# ngff-cardem.net
KiCad netlist of a schematic drawn in EAGLE
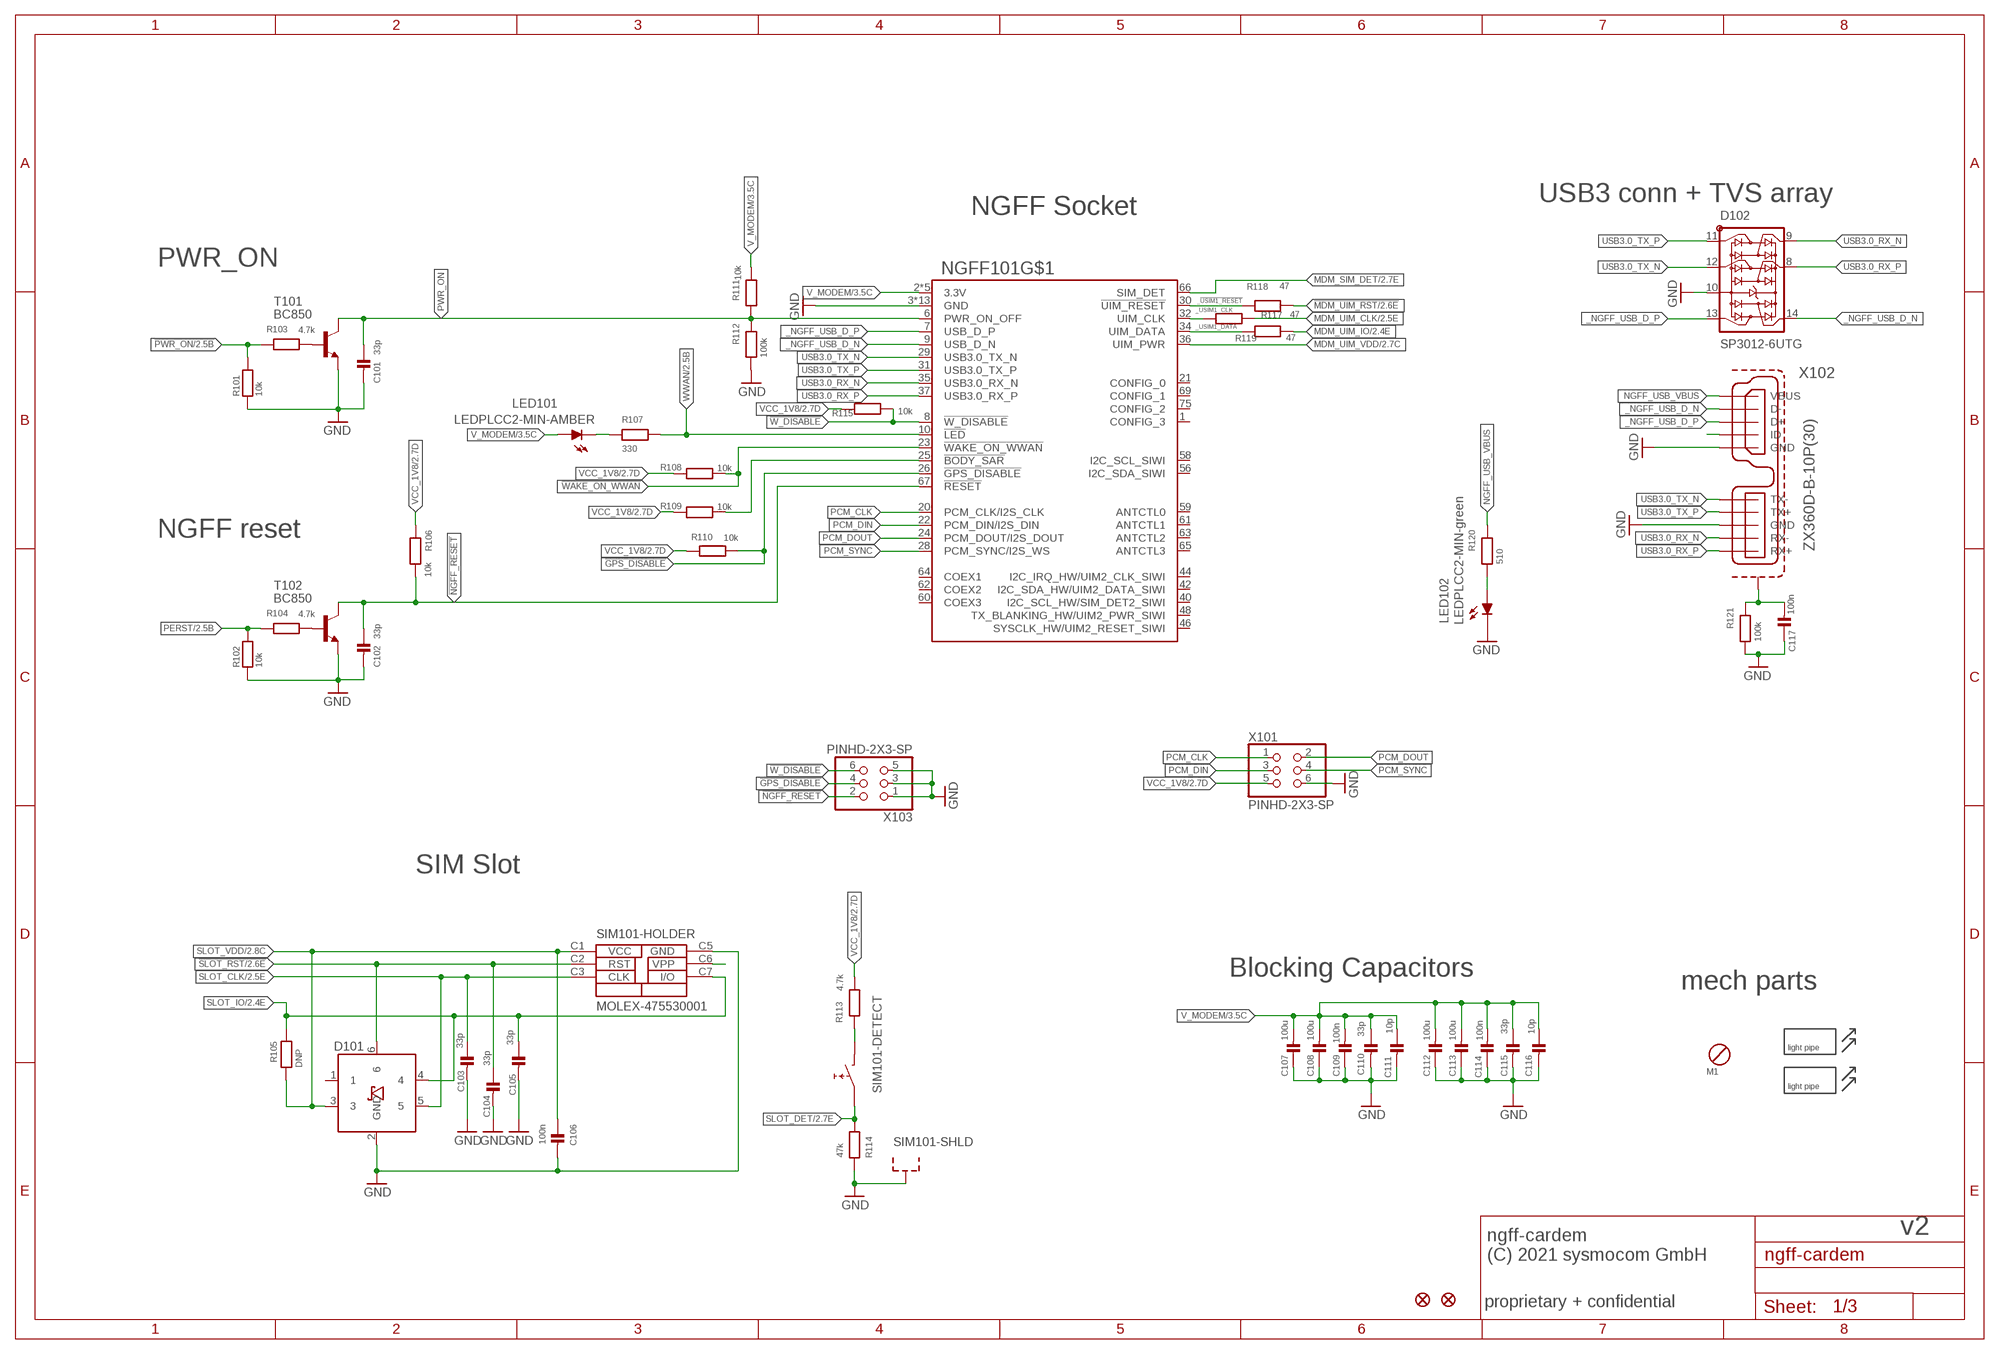
[diagram p0: schematic, sheet 1]
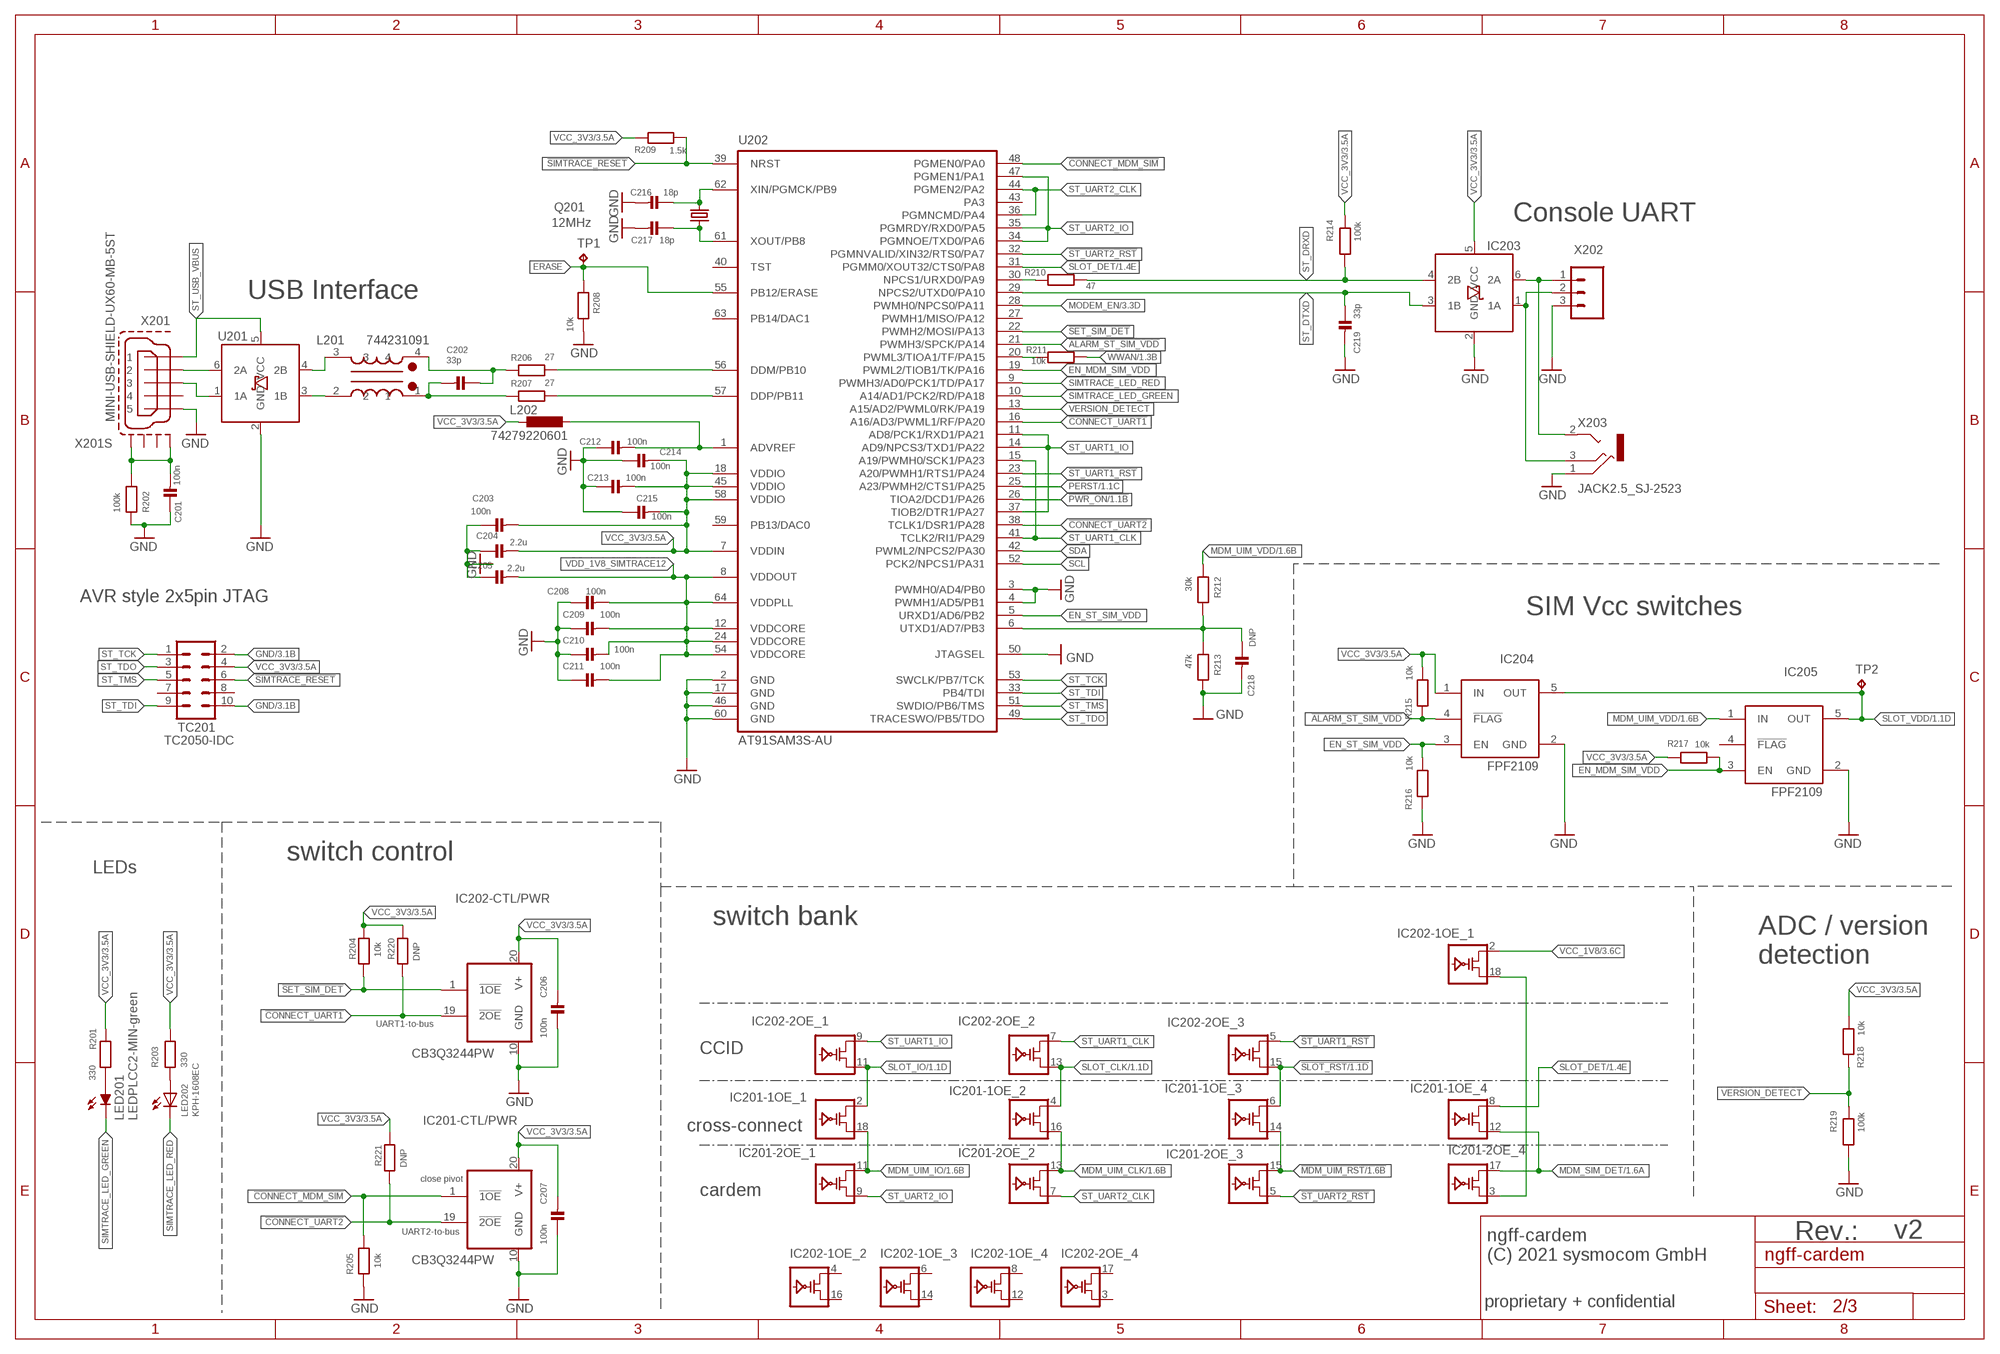
[diagram p1: schematic, sheet 2]
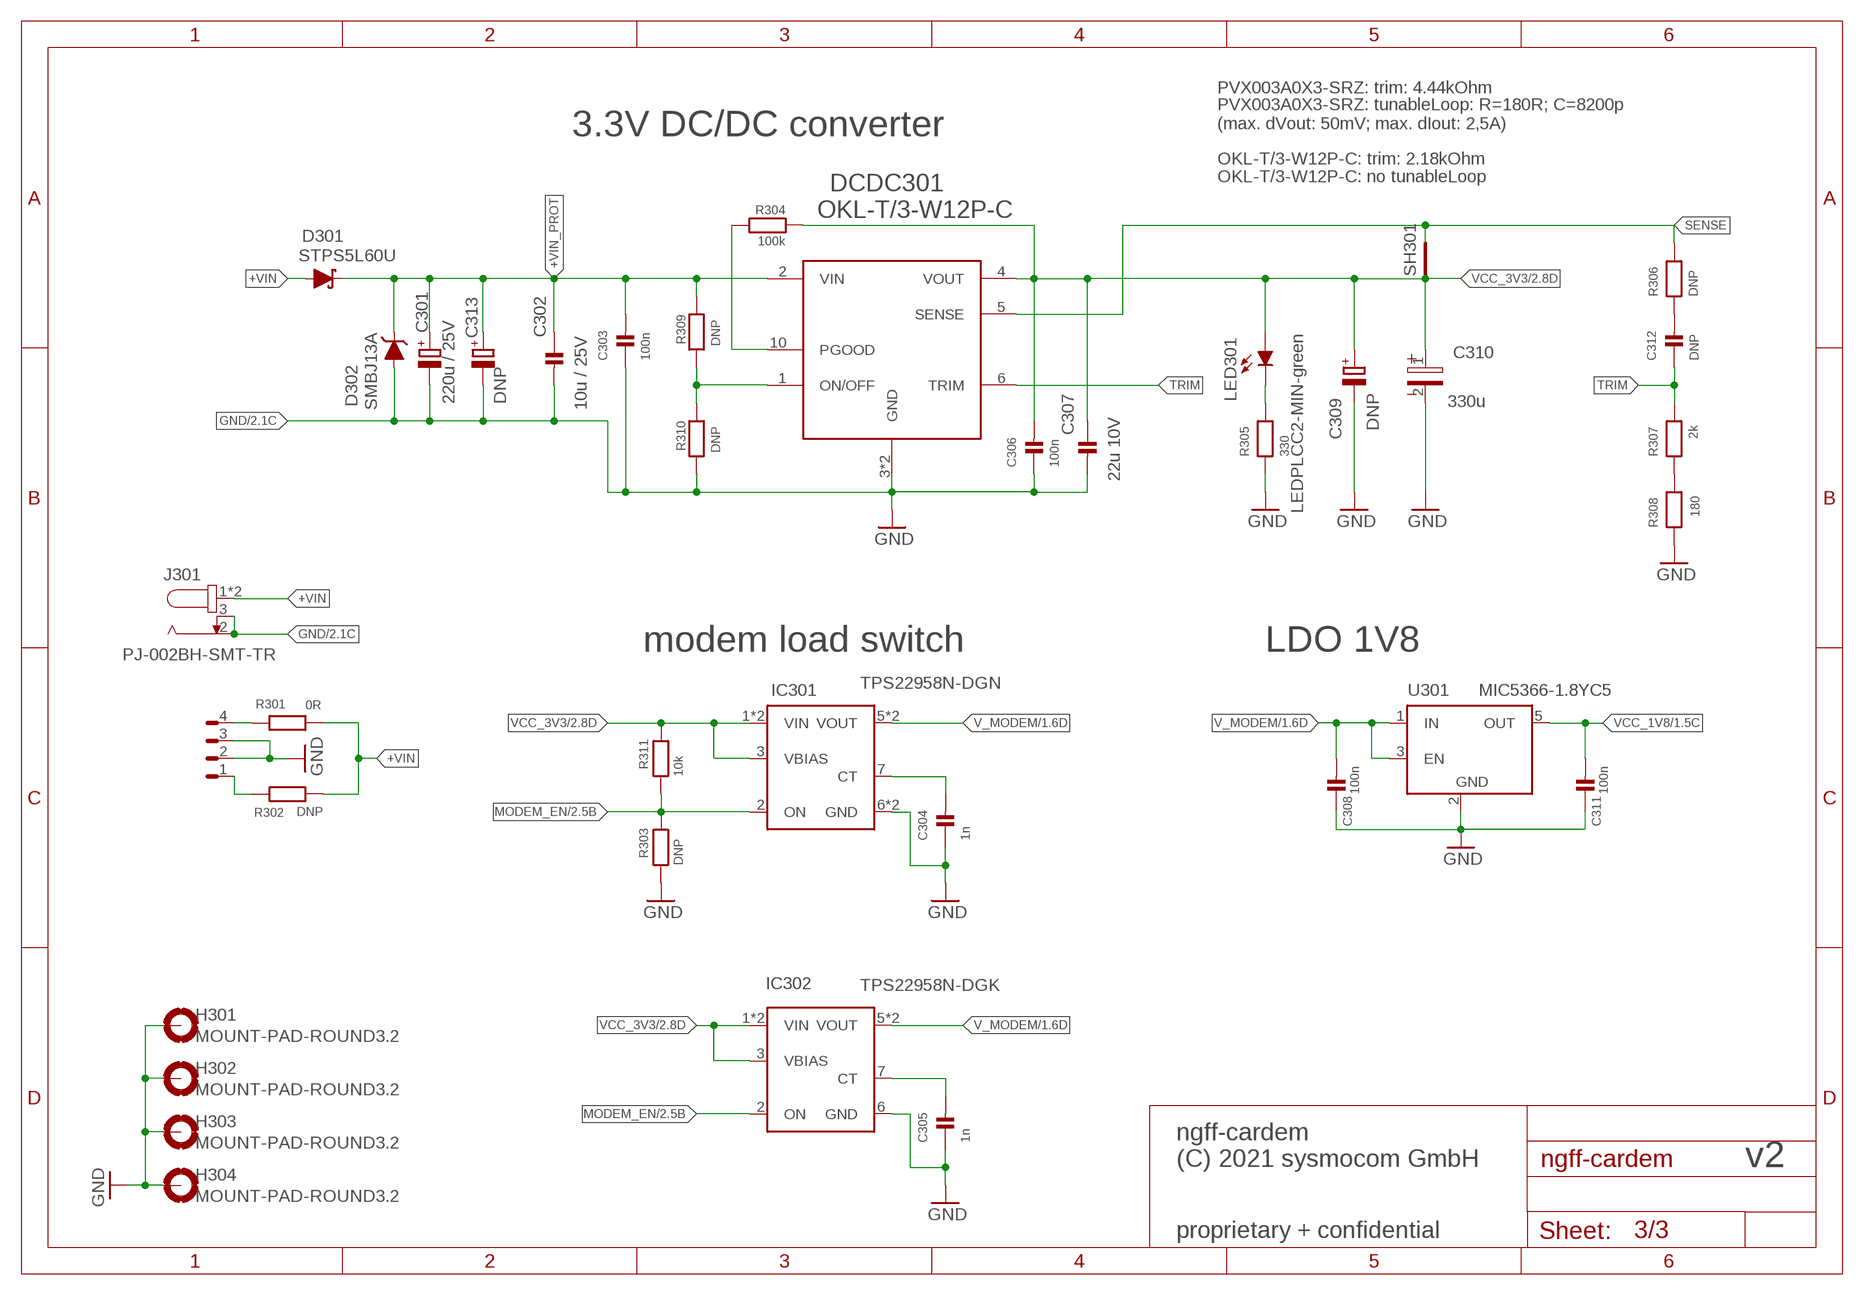
[diagram p2: schematic, sheet 3]

(export (version "E")
  (design (tool "Eeschema 10.0.6"))
  (components
    (comp (ref "C101")
      (value "33p")
      (footprint "eagle-import:_0402")
      (description "CAP CER 33PF 50V NP0 0402")
      (fields
        (field (name "MANUFACTURER") "Samsung Electro-Mechanics America, Inc.")
        (field (name "MANUFACTURERPARTNUMBER") "CL05C330JB5NNNC")
      )
      (libsource (lib "eagle-import") (part "CAP_CERAMIC_0402"))
    )
    (comp (ref "C102")
      (value "33p")
      (footprint "eagle-import:_0402")
      (description "CAP CER 33PF 50V NP0 0402")
      (fields
        (field (name "MANUFACTURER") "Samsung Electro-Mechanics America, Inc.")
        (field (name "MANUFACTURERPARTNUMBER") "CL05C330JB5NNNC")
      )
      (libsource (lib "eagle-import") (part "CAP_CERAMIC_0402"))
    )
    (comp (ref "C103")
      (value "33p")
      (footprint "eagle-import:_0402")
      (description "CAP CER 33PF 50V NP0 0402")
      (fields
        (field (name "MANUFACTURER") "Samsung Electro-Mechanics America, Inc.")
        (field (name "MANUFACTURERPARTNUMBER") "CL05C330JB5NNNC")
      )
      (libsource (lib "eagle-import") (part "CAP_CERAMIC_0402"))
    )
    (comp (ref "C104")
      (value "33p")
      (footprint "eagle-import:_0402")
      (description "CAP CER 33PF 50V NP0 0402")
      (fields
        (field (name "MANUFACTURER") "Samsung Electro-Mechanics America, Inc.")
        (field (name "MANUFACTURERPARTNUMBER") "CL05C330JB5NNNC")
      )
      (libsource (lib "eagle-import") (part "CAP_CERAMIC_0402"))
    )
    (comp (ref "C105")
      (value "33p")
      (footprint "eagle-import:_0402")
      (description "CAP CER 33PF 50V NP0 0402")
      (fields
        (field (name "MANUFACTURER") "Samsung Electro-Mechanics America, Inc.")
        (field (name "MANUFACTURERPARTNUMBER") "CL05C330JB5NNNC")
      )
      (libsource (lib "eagle-import") (part "CAP_CERAMIC_0402"))
    )
    (comp (ref "C106")
      (value "100n")
      (footprint "eagle-import:_0603")
      (description "CAP CER 0.1UF 16V X7R 0603")
      (fields
        (field (name "MANUFACTURER") "Yageo")
        (field (name "MANUFACTURERPARTNUMBER") "CC0603KRX7R7BB104")
      )
      (libsource (lib "eagle-import") (part "CAP_CERAMIC_0603"))
    )
    (comp (ref "C107")
      (value "100u")
      (footprint "eagle-import:1206")
      (description "CAP CER 100UF 6.3V X5R 1206")
      (fields
        (field (name "MANUFACTURER") "TDK Corporation")
        (field (name "MANUFACTURERPARTNUMBER") "C3216X5R0J107M160AB")
      )
      (libsource (lib "eagle-import") (part "CAP_CERAMIC1206"))
    )
    (comp (ref "C108")
      (value "100u")
      (footprint "eagle-import:1206")
      (description "CAP CER 100UF 6.3V X5R 1206")
      (fields
        (field (name "MANUFACTURER") "TDK Corporation")
        (field (name "MANUFACTURERPARTNUMBER") "C3216X5R0J107M160AB")
      )
      (libsource (lib "eagle-import") (part "CAP_CERAMIC1206"))
    )
    (comp (ref "C109")
      (value "100n")
      (footprint "eagle-import:_0603")
      (description "CAP CER 0.1UF 16V X7R 0603")
      (fields
        (field (name "MANUFACTURER") "Yageo")
        (field (name "MANUFACTURERPARTNUMBER") "CC0603KRX7R7BB104")
      )
      (libsource (lib "eagle-import") (part "CAP_CERAMIC_0603"))
    )
    (comp (ref "C110")
      (value "33p")
      (footprint "eagle-import:_0402")
      (description "CAP CER 33PF 50V NP0 0402")
      (fields
        (field (name "MANUFACTURER") "Samsung Electro-Mechanics America, Inc.")
        (field (name "MANUFACTURERPARTNUMBER") "CL05C330JB5NNNC")
      )
      (libsource (lib "eagle-import") (part "CAP_CERAMIC_0402"))
    )
    (comp (ref "C111")
      (value "10p")
      (footprint "eagle-import:_0603")
      (description "CAP CER 10PF 50V C0G/NP0 0603")
      (fields
        (field (name "MANUFACTURER") "KEMET")
        (field (name "MANUFACTURERPARTNUMBER") "C0603C100F5GAC7867")
      )
      (libsource (lib "eagle-import") (part "CAP_CERAMIC_0603"))
    )
    (comp (ref "C112")
      (value "100u")
      (footprint "eagle-import:1206")
      (description "CAP CER 100UF 6.3V X5R 1206")
      (fields
        (field (name "MANUFACTURER") "TDK Corporation")
        (field (name "MANUFACTURERPARTNUMBER") "C3216X5R0J107M160AB")
      )
      (libsource (lib "eagle-import") (part "CAP_CERAMIC1206"))
    )
    (comp (ref "C113")
      (value "100u")
      (footprint "eagle-import:1206")
      (description "CAP CER 100UF 6.3V X5R 1206")
      (fields
        (field (name "MANUFACTURER") "TDK Corporation")
        (field (name "MANUFACTURERPARTNUMBER") "C3216X5R0J107M160AB")
      )
      (libsource (lib "eagle-import") (part "CAP_CERAMIC1206"))
    )
    (comp (ref "C114")
      (value "100n")
      (footprint "eagle-import:_0603")
      (description "CAP CER 0.1UF 16V X7R 0603")
      (fields
        (field (name "MANUFACTURER") "Yageo")
        (field (name "MANUFACTURERPARTNUMBER") "CC0603KRX7R7BB104")
      )
      (libsource (lib "eagle-import") (part "CAP_CERAMIC_0603"))
    )
    (comp (ref "C115")
      (value "33p")
      (footprint "eagle-import:_0402")
      (description "CAP CER 33PF 50V NP0 0402")
      (fields
        (field (name "MANUFACTURER") "Samsung Electro-Mechanics America, Inc.")
        (field (name "MANUFACTURERPARTNUMBER") "CL05C330JB5NNNC")
      )
      (libsource (lib "eagle-import") (part "CAP_CERAMIC_0402"))
    )
    (comp (ref "C116")
      (value "10p")
      (footprint "eagle-import:_0603")
      (description "CAP CER 10PF 50V C0G/NP0 0603")
      (fields
        (field (name "MANUFACTURER") "KEMET")
        (field (name "MANUFACTURERPARTNUMBER") "C0603C100F5GAC7867")
      )
      (libsource (lib "eagle-import") (part "CAP_CERAMIC_0603"))
    )
    (comp (ref "C117")
      (value "100n")
      (footprint "eagle-import:_0603")
      (description "CAP CER 0.1UF 16V X7R 0603")
      (fields
        (field (name "MANUFACTURER") "Yageo")
        (field (name "MANUFACTURERPARTNUMBER") "CC0603KRX7R7BB104")
      )
      (libsource (lib "eagle-import") (part "CAP_CERAMIC_0603"))
    )
    (comp (ref "D101")
      (value "PESD5V0UBV")
      (footprint "eagle-import:SOT666")
      (description "TVS DIODE 5V SOT666")
      (fields
        (field (name "MANUFACTURER") "Nexperia USA Inc.")
        (field (name "MANUFACTURERPARTNUMBER") "PESD5V0U5BV,115")
      )
      (libsource (lib "eagle-import") (part "PESD5V0UBV"))
    )
    (comp (ref "D102")
      (value "SP3012-6UTG")
      (footprint "eagle-import:UDFN-14")
      (description "TVS DIODE 5V 7V 14UDFN")
      (fields
        (field (name "MANUFACTURER") "Littelfuse Inc.")
        (field (name "MANUFACTURERPARTNUMBER") "SP3012-06UTG")
      )
      (libsource (lib "eagle-import") (part "SP3012-6UTG"))
    )
    (comp (ref "JP102")
      (value "FIDUCIALUFIDUCIAL")
      (footprint "eagle-import:MICRO-FIDUCIAL")
      (description "NO DESCRIPTION")
      (fields
        (field (name "MANUFACTURER") "UNKNOWN MANUFACTURER")
        (field (name "MANUFACTURERPARTNUMBER") "UNKNOWN MANUFACTURER PART NUMBER")
      )
      (libsource (lib "eagle-import") (part "FIDUCIALUFIDUCIAL"))
    )
    (comp (ref "JP103")
      (value "FIDUCIALUFIDUCIAL")
      (footprint "eagle-import:MICRO-FIDUCIAL")
      (description "NO DESCRIPTION")
      (fields
        (field (name "MANUFACTURER") "UNKNOWN MANUFACTURER")
        (field (name "MANUFACTURERPARTNUMBER") "UNKNOWN MANUFACTURER PART NUMBER")
      )
      (libsource (lib "eagle-import") (part "FIDUCIALUFIDUCIAL"))
    )
    (comp (ref "LED101")
      (value "LEDPLCC2-MIN-AMBER")
      (footprint "eagle-import:PLCC2-MIN")
      (description "LED ORANGE CLEAR 2PLCC SMD")
      (fields
        (field (name "MANUFACTURER") "OSRAM Opto Semiconductors Inc.")
        (field (name "MANUFACTURERPARTNUMBER") "LO T676-S1T1-24-Z")
      )
      (libsource (lib "eagle-import") (part "LEDPLCC2-MIN"))
    )
    (comp (ref "LED102")
      (value "LEDPLCC2-MIN-green")
      (footprint "eagle-import:PLCC2-MIN")
      (description "LED GREEN CLEAR 2PLCC SMD")
      (fields
        (field (name "MANUFACTURER") "Broadcom Limited")
        (field (name "MANUFACTURERPARTNUMBER") "HSME-A100-M02J1")
      )
      (libsource (lib "eagle-import") (part "LEDPLCC2-MIN"))
    )
    (comp (ref "M2")
      (value "MENTOR_12701001")
      (footprint "eagle-import:1270.1001")
      (description "NO DESCRIPTION")
      (fields
        (field (name "MANUFACTURER") "UNKNOWN MANUFACTURER")
        (field (name "MANUFACTURERPARTNUMBER") "UNKNOWN MANUFACTURER PART NUMBER")
      )
      (libsource (lib "eagle-import") (part "MENTOR_12701001"))
    )
    (comp (ref "M3")
      (value "MENTOR_12701001")
      (footprint "eagle-import:1270.1001")
      (description "NO DESCRIPTION")
      (fields
        (field (name "MANUFACTURER") "UNKNOWN MANUFACTURER")
        (field (name "MANUFACTURERPARTNUMBER") "UNKNOWN MANUFACTURER PART NUMBER")
      )
      (libsource (lib "eagle-import") (part "MENTOR_12701001"))
    )
    (comp (ref "NGFF101")
      (value "NGFF_B-NSOL")
      (footprint "eagle-import:NGFF_3042_3052_NSOL")
      (description "CONN FEMALE 67POS 0.020 GOLD")
      (fields
        (field (name "MANUFACTURER") "TE Connectivity AMP Connectors")
        (field (name "MANUFACTURERPARTNUMBER") "2199230-3")
      )
      (libsource (lib "eagle-import") (part "NGFF_B-NSOL"))
    )
    (comp (ref "R101")
      (value "10k")
      (footprint "eagle-import:_0603")
      (description "RES SMD 10K OHM 1%% 1/10W 0603")
      (fields
        (field (name "MANUFACTURER") "TE Connectivity Passive Product")
        (field (name "MANUFACTURERPARTNUMBER") "CRG0603F10K/10")
      )
      (libsource (lib "eagle-import") (part "RESISTOR_0603"))
    )
    (comp (ref "R102")
      (value "10k")
      (footprint "eagle-import:_0603")
      (description "RES SMD 10K OHM 1%% 1/10W 0603")
      (fields
        (field (name "MANUFACTURER") "TE Connectivity Passive Product")
        (field (name "MANUFACTURERPARTNUMBER") "CRG0603F10K/10")
      )
      (libsource (lib "eagle-import") (part "RESISTOR_0603"))
    )
    (comp (ref "R103")
      (value "4.7k")
      (footprint "eagle-import:_0603")
      (description "RES SMD 4.7K OHM 5% 1/10W 0603")
      (fields (field (name "MANUFACTURER") "Yageo") (field (name "MANUFACTURERPARTNUMBER") "RC0603JR-074K7L"))
      (libsource (lib "eagle-import") (part "RESISTOR_0603"))
    )
    (comp (ref "R104")
      (value "4.7k")
      (footprint "eagle-import:_0603")
      (description "RES SMD 4.7K OHM 5% 1/10W 0603")
      (fields (field (name "MANUFACTURER") "Yageo") (field (name "MANUFACTURERPARTNUMBER") "RC0603JR-074K7L"))
      (libsource (lib "eagle-import") (part "RESISTOR_0603"))
    )
    (comp (ref "R105")
      (value "DNP")
      (footprint "eagle-import:_0603")
      (description "RES SMD 10K OHM 1%% 1/10W 0603")
      (fields
        (field (name "MANUFACTURER") "TE Connectivity Passive Product")
        (field (name "MANUFACTURERPARTNUMBER") "CRG0603F10K/10")
      )
      (libsource (lib "eagle-import") (part "RESISTOR_0603"))
    )
    (comp (ref "R106")
      (value "10k")
      (footprint "eagle-import:_0603")
      (description "RES SMD 10K OHM 1%% 1/10W 0603")
      (fields
        (field (name "MANUFACTURER") "TE Connectivity Passive Product")
        (field (name "MANUFACTURERPARTNUMBER") "CRG0603F10K/10")
      )
      (libsource (lib "eagle-import") (part "RESISTOR_0603"))
    )
    (comp (ref "R107")
      (value "330")
      (footprint "eagle-import:_0603")
      (description "RES SMD 330 OHM 1%% 1/10W 0603")
      (fields
        (field (name "MANUFACTURER") "Yageo")
        (field (name "MANUFACTURERPARTNUMBER") "RC0603FR-07330RL")
      )
      (libsource (lib "eagle-import") (part "RESISTOR_0603"))
    )
    (comp (ref "R108")
      (value "10k")
      (footprint "eagle-import:_0603")
      (description "RES SMD 10K OHM 1%% 1/10W 0603")
      (fields
        (field (name "MANUFACTURER") "TE Connectivity Passive Product")
        (field (name "MANUFACTURERPARTNUMBER") "CRG0603F10K/10")
      )
      (libsource (lib "eagle-import") (part "RESISTOR_0603"))
    )
    (comp (ref "R109")
      (value "10k")
      (footprint "eagle-import:_0603")
      (description "RES SMD 10K OHM 1%% 1/10W 0603")
      (fields
        (field (name "MANUFACTURER") "TE Connectivity Passive Product")
        (field (name "MANUFACTURERPARTNUMBER") "CRG0603F10K/10")
      )
      (libsource (lib "eagle-import") (part "RESISTOR_0603"))
    )
    (comp (ref "R110")
      (value "10k")
      (footprint "eagle-import:_0603")
      (description "RES SMD 10K OHM 1%% 1/10W 0603")
      (fields
        (field (name "MANUFACTURER") "TE Connectivity Passive Product")
        (field (name "MANUFACTURERPARTNUMBER") "CRG0603F10K/10")
      )
      (libsource (lib "eagle-import") (part "RESISTOR_0603"))
    )
    (comp (ref "R111")
      (value "10k")
      (footprint "eagle-import:_0603")
      (description "RES SMD 10K OHM 1%% 1/10W 0603")
      (fields
        (field (name "MANUFACTURER") "TE Connectivity Passive Product")
        (field (name "MANUFACTURERPARTNUMBER") "CRG0603F10K/10")
      )
      (libsource (lib "eagle-import") (part "RESISTOR_0603"))
    )
    (comp (ref "R112")
      (value "100k")
      (footprint "eagle-import:_0603")
      (description "RES 100K OHM 1%% 1/10W 0603")
      (fields
        (field (name "MANUFACTURER") "Stackpole Electronics Inc")
        (field (name "MANUFACTURERPARTNUMBER") "RMCF0603FT100K")
      )
      (libsource (lib "eagle-import") (part "RESISTOR_0603"))
    )
    (comp (ref "R113")
      (value "4.7k")
      (footprint "eagle-import:_0603")
      (description "RES SMD 4.7K OHM 5% 1/10W 0603")
      (fields (field (name "MANUFACTURER") "Yageo") (field (name "MANUFACTURERPARTNUMBER") "RC0603JR-074K7L"))
      (libsource (lib "eagle-import") (part "RESISTOR_0603"))
    )
    (comp (ref "R114")
      (value "47k")
      (footprint "eagle-import:_0603")
      (description "RES 47K OHM 1%% 1/10W 0603")
      (fields
        (field (name "MANUFACTURER") "Stackpole Electronics Inc")
        (field (name "MANUFACTURERPARTNUMBER") "RMCF0603FT47K0")
      )
      (libsource (lib "eagle-import") (part "RESISTOR_0603"))
    )
    (comp (ref "R115")
      (value "10k")
      (footprint "eagle-import:_0603")
      (description "RES SMD 10K OHM 1%% 1/10W 0603")
      (fields
        (field (name "MANUFACTURER") "TE Connectivity Passive Product")
        (field (name "MANUFACTURERPARTNUMBER") "CRG0603F10K/10")
      )
      (libsource (lib "eagle-import") (part "RESISTOR_0603"))
    )
    (comp (ref "R117")
      (value "47")
      (footprint "eagle-import:_0402")
      (description "RES SMD 47R 0402 1%")
      (fields
        (field (name "MANUFACTURER") "TE Connectivity Passive Product")
        (field (name "MANUFACTURERPARTNUMBER") "CRGCQ0402F47R")
      )
      (libsource (lib "eagle-import") (part "RESISTOR_0402"))
    )
    (comp (ref "R118")
      (value "47")
      (footprint "eagle-import:_0402")
      (description "RES SMD 47R 0402 1%")
      (fields
        (field (name "MANUFACTURER") "TE Connectivity Passive Product")
        (field (name "MANUFACTURERPARTNUMBER") "CRGCQ0402F47R")
      )
      (libsource (lib "eagle-import") (part "RESISTOR_0402"))
    )
    (comp (ref "R119")
      (value "47")
      (footprint "eagle-import:_0402")
      (description "RES SMD 47R 0402 1%")
      (fields
        (field (name "MANUFACTURER") "TE Connectivity Passive Product")
        (field (name "MANUFACTURERPARTNUMBER") "CRGCQ0402F47R")
      )
      (libsource (lib "eagle-import") (part "RESISTOR_0402"))
    )
    (comp (ref "R120")
      (value "510")
      (footprint "eagle-import:_0603")
      (description "RES 510 OHM 1%% 1/10W 0603")
      (fields
        (field (name "MANUFACTURER") "Stackpole Electronics Inc")
        (field (name "MANUFACTURERPARTNUMBER") "RMCF0603FT510R")
      )
      (libsource (lib "eagle-import") (part "RESISTOR_0603"))
    )
    (comp (ref "R121")
      (value "100k")
      (footprint "eagle-import:_0603")
      (description "RES 100K OHM 1%% 1/10W 0603")
      (fields
        (field (name "MANUFACTURER") "Stackpole Electronics Inc")
        (field (name "MANUFACTURERPARTNUMBER") "RMCF0603FT100K")
      )
      (libsource (lib "eagle-import") (part "RESISTOR_0603"))
    )
    (comp (ref "SIM101")
      (value "MOLEX-475530001")
      (footprint "eagle-import:MOLEX-475530001")
      (description "CONN SIM CARD PUSH-PUSH R/A SMD")
      (fields
        (field (name "CLASS") "SIM HOLDER")
        (field (name "LINK") "https://www.digikey.de/product-detail/de/molex/0475530001/WM3293TR-ND/2404889")
        (field (name "MANUFACTURER") "Molex")
        (field (name "MANUFACTURERPARTNUMBER") "0475530001")
        (field (name "POPULATED") "TRUE")
        (field (name "ROHSCERTIFICATE") "RoHS3-konform")
        (field (name "SOURCE") "DIGIKEY")
        (field (name "SOURCEPARTNUMBER") "WM3293TR-ND")
      )
      (libsource (lib "eagle-import") (part "MOLEX-475530001"))
    )
    (comp (ref "T101")
      (value "BC850")
      (footprint "eagle-import:SOT23-BEC")
      (description "TRANS NPN 45V 100MA TO236AB")
      (fields
        (field (name "MANUFACTURER") "Nexperia USA Inc.")
        (field (name "MANUFACTURERPARTNUMBER") "BC850C,235")
      )
      (libsource (lib "eagle-import") (part "-NPN-SOT23-BECBC847C"))
    )
    (comp (ref "T102")
      (value "BC850")
      (footprint "eagle-import:SOT23-BEC")
      (description "TRANS NPN 45V 100MA TO236AB")
      (fields
        (field (name "MANUFACTURER") "Nexperia USA Inc.")
        (field (name "MANUFACTURERPARTNUMBER") "BC850C,235")
      )
      (libsource (lib "eagle-import") (part "-NPN-SOT23-BECBC847C"))
    )
    (comp (ref "X101")
      (value "PINHD-2X3-SP")
      (footprint "eagle-import:2X03")
      (description "PIN HEADER, THR, DUAL ROW, .100\"")
      (fields
        (field (name "MANUFACTURER") "METZ CONNECT USA Inc.")
        (field (name "MANUFACTURERPARTNUMBER") "PR20203VBDN")
      )
      (libsource (lib "eagle-import") (part "PINHD-2X3"))
    )
    (comp (ref "X102")
      (value "ZX360D-B-10P(30)")
      (footprint "eagle-import:ZX360D-B")
      (description "CONN RCPT USB3.0 MICRO B SMD R/A")
      (fields (field (name "MANUFACTURER") "Hirose Electric Co Ltd"))
      (libsource (lib "eagle-import") (part "USB3.0-MICROB"))
    )
    (comp (ref "X103")
      (value "PINHD-2X3-SP")
      (footprint "eagle-import:2X03")
      (description "PIN HEADER, THR, DUAL ROW, .100\"")
      (fields
        (field (name "MANUFACTURER") "METZ CONNECT USA Inc.")
        (field (name "MANUFACTURERPARTNUMBER") "PR20203VBDN")
      )
      (libsource (lib "eagle-import") (part "PINHD-2X3"))
    )
    (comp (ref "C301")
      (value "220u / 25V")
      (footprint "eagle-import:UD-8X10_NICHICON")
      (description "CAP ALUM 220UF 20%% 25V SMD")
      (fields
        (field (name "MANUFACTURER") "Nichicon")
        (field (name "MANUFACTURERPARTNUMBER") "UUD1E221MNL1GS")
      )
      (libsource (lib "eagle-import") (part "CPOL-EUUD-8X10"))
    )
    (comp (ref "C302")
      (value "10u / 25V")
      (footprint "eagle-import:C1812K")
      (description "CAP CER 10UF 25V X7R 1812")
      (fields
        (field (name "MANUFACTURER") "TDK Corporation")
        (field (name "MANUFACTURERPARTNUMBER") "C4532X7R1E106M250KA")
      )
      (libsource (lib "eagle-import") (part "CAP_CERAMIC-C1812"))
    )
    (comp (ref "C303")
      (value "100n")
      (footprint "eagle-import:_0603")
      (description "CAP CER 0.1UF 16V X7R 0603")
      (fields
        (field (name "MANUFACTURER") "Yageo")
        (field (name "MANUFACTURERPARTNUMBER") "CC0603KRX7R7BB104")
      )
      (libsource (lib "eagle-import") (part "CAP_CERAMIC_0603"))
    )
    (comp (ref "C304")
      (value "1n")
      (footprint "eagle-import:_0603")
      (description "CAP CER 1000PF 50V X7R 0603")
      (fields
        (field (name "MANUFACTURER") "Samsung Electro-Mechanics")
        (field (name "MANUFACTURERPARTNUMBER") "CL10B102KB8NNNC")
      )
      (libsource (lib "eagle-import") (part "CAP_CERAMIC_0603"))
    )
    (comp (ref "C305")
      (value "1n")
      (footprint "eagle-import:_0603")
      (description "CAP CER 1000PF 50V X7R 0603")
      (fields
        (field (name "MANUFACTURER") "Samsung Electro-Mechanics")
        (field (name "MANUFACTURERPARTNUMBER") "CL10B102KB8NNNC")
      )
      (libsource (lib "eagle-import") (part "CAP_CERAMIC_0603"))
    )
    (comp (ref "C306")
      (value "100n")
      (footprint "eagle-import:_0603")
      (description "CAP CER 0.1UF 16V X7R 0603")
      (fields
        (field (name "MANUFACTURER") "Yageo")
        (field (name "MANUFACTURERPARTNUMBER") "CC0603KRX7R7BB104")
      )
      (libsource (lib "eagle-import") (part "CAP_CERAMIC_0603"))
    )
    (comp (ref "C307")
      (value "22u 10V")
      (footprint "eagle-import:1206")
      (description "CAP CER 47UF 10V X5R 1206")
      (fields
        (field (name "MANUFACTURER") "Samsung Electro-Mechanics")
        (field (name "MANUFACTURERPARTNUMBER") "CL31A476MPHNNNE")
      )
      (libsource (lib "eagle-import") (part "CAP_CERAMIC1206"))
    )
    (comp (ref "C308")
      (value "100n")
      (footprint "eagle-import:_0603")
      (description "CAP CER 0.1UF 16V X7R 0603")
      (fields
        (field (name "MANUFACTURER") "Yageo")
        (field (name "MANUFACTURERPARTNUMBER") "CC0603KRX7R7BB104")
      )
      (libsource (lib "eagle-import") (part "CAP_CERAMIC_0603"))
    )
    (comp (ref "C309")
      (value "DNP")
      (footprint "eagle-import:SMC_B")
      (description "CAP TANT 100UF 6.3V 20% 1210")
      (fields
        (field (name "MANUFACTURER") "AVX Corporation")
        (field (name "MANUFACTURERPARTNUMBER") "F920J107MBA")
      )
      (libsource (lib "eagle-import") (part "CPOL-EUSMCB"))
    )
    (comp (ref "C310")
      (value "330u")
      (footprint "eagle-import:4.2X1.9X2.8(BXCXA)")
      (description "CAP ALUM POLY 330UF 20%% 6.3V SMD")
      (fields
        (field (name "MANUFACTURER") "United Chemi-Con")
        (field (name "MANUFACTURERPARTNUMBER") "APXF6R3ARA331MH70G")
      )
      (libsource (lib "eagle-import") (part "WCAP-PSLC_8X11.7(DXL)"))
    )
    (comp (ref "C311")
      (value "100n")
      (footprint "eagle-import:_0603")
      (description "CAP CER 0.1UF 16V X7R 0603")
      (fields
        (field (name "MANUFACTURER") "Yageo")
        (field (name "MANUFACTURERPARTNUMBER") "CC0603KRX7R7BB104")
      )
      (libsource (lib "eagle-import") (part "CAP_CERAMIC_0603"))
    )
    (comp (ref "C312")
      (value "DNP")
      (footprint "eagle-import:_0603")
      (description "NO DESCRIPTION")
      (fields
        (field (name "MANUFACTURER") "UNKNOWN MANUFACTURER")
        (field (name "MANUFACTURERPARTNUMBER") "UNKNOWN MANUFACTURER PART NUMBER")
      )
      (libsource (lib "eagle-import") (part "CAP_CERAMIC_0603"))
    )
    (comp (ref "C313")
      (value "DNP")
      (footprint "eagle-import:UD-8X10_NICHICON")
      (description "NO DESCRIPTION")
      (fields
        (field (name "MANUFACTURER") "UNKNOWN MANUFACTURER")
        (field (name "MANUFACTURERPARTNUMBER") "UNKNOWN MANUFACTURER PART NUMBER")
      )
      (libsource (lib "eagle-import") (part "CPOL-EUUD-8X10"))
    )
    (comp (ref "D301")
      (value "STPS5L60U")
      (footprint "eagle-import:SMBDIODE")
      (description "DIODE SCHOTTKY 50V 3A SMB")
      (fields
        (field (name "MANUFACTURER") "Diodes Incorporated")
        (field (name "MANUFACTURERPARTNUMBER") "B350B-13-F")
      )
      (libsource (lib "eagle-import") (part "DIODE-SCHOTTKY-SMB"))
    )
    (comp (ref "D302")
      (value "SMBJ13A")
      (footprint "eagle-import:SMBDIODE")
      (description "TVS DIODE 13.6VWM 22.5VC SMB")
      (fields
        (field (name "MANUFACTURER") "Littelfuse Inc.")
        (field (name "MANUFACTURERPARTNUMBER") "SZP6SMB16AT3G")
      )
      (libsource (lib "eagle-import") (part "DIODE-TVS-SMB"))
    )
    (comp (ref "DCDC301")
      (value "OKL-T/3-W12P-C")
      (footprint "eagle-import:DC-DC_CON-ALLPADS")
      (description "DC DC CONVERTER 0.591-5.5V 15W")
      (fields (field (name "MANUFACTURER") "Murata Power Solutions Inc."))
      (libsource (lib "eagle-import") (part "DCDC-GE-PVX-ALL"))
    )
    (comp (ref "H301")
      (value "MOUNT-PAD-ROUND3.2")
      (footprint "eagle-import:3,2-PAD")
      (description "NO DESCRIPTION")
      (fields
        (field (name "MANUFACTURER") "UNKNOWN MANUFACTURER")
        (field (name "MANUFACTURERPARTNUMBER") "UNKNOWN MANUFACTURER PART NUMBER")
      )
      (libsource (lib "eagle-import") (part "MOUNT-PAD-ROUND3.2"))
    )
    (comp (ref "H302")
      (value "MOUNT-PAD-ROUND3.2")
      (footprint "eagle-import:3,2-PAD")
      (description "NO DESCRIPTION")
      (fields
        (field (name "MANUFACTURER") "UNKNOWN MANUFACTURER")
        (field (name "MANUFACTURERPARTNUMBER") "UNKNOWN MANUFACTURER PART NUMBER")
      )
      (libsource (lib "eagle-import") (part "MOUNT-PAD-ROUND3.2"))
    )
    (comp (ref "H303")
      (value "MOUNT-PAD-ROUND3.2")
      (footprint "eagle-import:3,2-PAD")
      (description "NO DESCRIPTION")
      (fields
        (field (name "MANUFACTURER") "UNKNOWN MANUFACTURER")
        (field (name "MANUFACTURERPARTNUMBER") "UNKNOWN MANUFACTURER PART NUMBER")
      )
      (libsource (lib "eagle-import") (part "MOUNT-PAD-ROUND3.2"))
    )
    (comp (ref "H304")
      (value "MOUNT-PAD-ROUND3.2")
      (footprint "eagle-import:3,2-PAD")
      (description "NO DESCRIPTION")
      (fields
        (field (name "MANUFACTURER") "UNKNOWN MANUFACTURER")
        (field (name "MANUFACTURERPARTNUMBER") "UNKNOWN MANUFACTURER PART NUMBER")
      )
      (libsource (lib "eagle-import") (part "MOUNT-PAD-ROUND3.2"))
    )
    (comp (ref "IC301")
      (value "TPS22958N-DGN")
      (footprint "eagle-import:HVSSOP8")
      (description "IC PWR SWITCH N-CHAN 1:1 8MSOP")
      (fields
        (field (name "MANUFACTURER") "Texas Instruments")
        (field (name "MANUFACTURERPARTNUMBER") "TPS22958DGNR")
      )
      (libsource (lib "eagle-import") (part "TPS22958-DGNN"))
    )
    (comp (ref "IC302")
      (value "TPS22958N-DGK")
      (footprint "eagle-import:VSSOP8")
      (description "IC PWR SWITCH N-CHAN 1:1 8VSSOP")
      (fields
        (field (name "MANUFACTURER") "Texas Instruments")
        (field (name "MANUFACTURERPARTNUMBER") "TPS22958NDGKR")
      )
      (libsource (lib "eagle-import") (part "TPS22958-DGKN"))
    )
    (comp (ref "J301")
      (value "PJ-002BH-SMT-TR")
      (footprint "eagle-import:694108106102")
      (description "CONN PWR JACK 2.5X5.5MM SOLDER")
      (fields (field (name "MANUFACTURER") "CUI Devices"))
      (libsource (lib "eagle-import") (part "694108106102"))
    )
    (comp (ref "LED301")
      (value "LEDPLCC2-MIN-green")
      (footprint "eagle-import:PLCC2-MIN")
      (description "LED GREEN CLEAR 2PLCC SMD")
      (fields
        (field (name "MANUFACTURER") "Broadcom Limited")
        (field (name "MANUFACTURERPARTNUMBER") "HSME-A100-M02J1")
      )
      (libsource (lib "eagle-import") (part "LEDPLCC2-MIN"))
    )
    (comp (ref "R301")
      (value "0R")
      (footprint "eagle-import:1210")
      (description "RES 0 OHM JUMPER 1206")
      (fields
        (field (name "MANUFACTURER") "KOA Speer Electronics, Inc.")
        (field (name "MANUFACTURERPARTNUMBER") "TLRZ2BTTD")
      )
      (libsource (lib "eagle-import") (part "RESISTOR1210"))
    )
    (comp (ref "R302")
      (value "DNP")
      (footprint "eagle-import:1210")
      (description "RES 0 OHM JUMPER 1206")
      (fields
        (field (name "MANUFACTURER") "KOA Speer Electronics, Inc.")
        (field (name "MANUFACTURERPARTNUMBER") "TLRZ2BTTD")
      )
      (libsource (lib "eagle-import") (part "RESISTOR1210"))
    )
    (comp (ref "R303")
      (value "DNP")
      (footprint "eagle-import:_0603")
      (description "NO DESCRIPTION")
      (fields
        (field (name "MANUFACTURER") "UNKNOWN MANUFACTURER")
        (field (name "MANUFACTURERPARTNUMBER") "UNKNOWN MANUFACTURER PART NUMBER")
      )
      (libsource (lib "eagle-import") (part "RESISTOR_0603"))
    )
    (comp (ref "R304")
      (value "100k")
      (footprint "eagle-import:_0603")
      (description "RES 100K OHM 1%% 1/10W 0603")
      (fields
        (field (name "MANUFACTURER") "Stackpole Electronics Inc")
        (field (name "MANUFACTURERPARTNUMBER") "RMCF0603FT100K")
      )
      (libsource (lib "eagle-import") (part "RESISTOR_0603"))
    )
    (comp (ref "R305")
      (value "330")
      (footprint "eagle-import:_0603")
      (description "RES SMD 330 OHM 1%% 1/10W 0603")
      (fields
        (field (name "MANUFACTURER") "Yageo")
        (field (name "MANUFACTURERPARTNUMBER") "RC0603FR-07330RL")
      )
      (libsource (lib "eagle-import") (part "RESISTOR_0603"))
    )
    (comp (ref "R306")
      (value "DNP")
      (footprint "eagle-import:_0603")
      (description "NO DESCRIPTION")
      (fields
        (field (name "MANUFACTURER") "UNKNOWN MANUFACTURER")
        (field (name "MANUFACTURERPARTNUMBER") "UNKNOWN MANUFACTURER PART NUMBER")
      )
      (libsource (lib "eagle-import") (part "RESISTOR_0603"))
    )
    (comp (ref "R307")
      (value "2k")
      (footprint "eagle-import:_0603")
      (description "RES SMD 2K OHM 1% 1/10W 0603")
      (fields (field (name "MANUFACTURER") "YAGEO") (field (name "MANUFACTURERPARTNUMBER") "RC0603FR-072KL"))
      (libsource (lib "eagle-import") (part "RESISTOR_0603"))
    )
    (comp (ref "R308")
      (value "180")
      (footprint "eagle-import:_0603")
      (description "RES SMD 180R 1% 1/10W 0603")
      (fields
        (field (name "MANUFACTURER") "TE Connectivity Passive Product")
        (field (name "MANUFACTURERPARTNUMBER") "CRGCQ0603F180R")
      )
      (libsource (lib "eagle-import") (part "RESISTOR_0603"))
    )
    (comp (ref "R309")
      (value "DNP")
      (footprint "eagle-import:_0603")
      (description "NO DESCRIPTION")
      (fields
        (field (name "MANUFACTURER") "UNKNOWN MANUFACTURER")
        (field (name "MANUFACTURERPARTNUMBER") "UNKNOWN MANUFACTURER PART NUMBER")
      )
      (libsource (lib "eagle-import") (part "RESISTOR_0603"))
    )
    (comp (ref "R310")
      (value "DNP")
      (footprint "eagle-import:_0603")
      (description "NO DESCRIPTION")
      (fields
        (field (name "MANUFACTURER") "UNKNOWN MANUFACTURER")
        (field (name "MANUFACTURERPARTNUMBER") "UNKNOWN MANUFACTURER PART NUMBER")
      )
      (libsource (lib "eagle-import") (part "RESISTOR_0603"))
    )
    (comp (ref "R311")
      (value "10k")
      (footprint "eagle-import:_0603")
      (description "RES SMD 10K OHM 1%% 1/10W 0603")
      (fields
        (field (name "MANUFACTURER") "TE Connectivity Passive Product")
        (field (name "MANUFACTURERPARTNUMBER") "CRG0603F10K/10")
      )
      (libsource (lib "eagle-import") (part "RESISTOR_0603"))
    )
    (comp (ref "SH301")
      (value "SHORT-HT5")
      (footprint "eagle-import:SHORT_TOP-50")
      (description "NO DESCRIPTION")
      (fields
        (field (name "MANUFACTURER") "UNKNOWN MANUFACTURER")
        (field (name "MANUFACTURERPARTNUMBER") "UNKNOWN MANUFACTURER PART NUMBER")
      )
      (libsource (lib "eagle-import") (part "SHORT-HT5"))
    )
    (comp (ref "U301")
      (value "MIC5366-1.8YC5")
      (footprint "eagle-import:SC70-5")
      (description "IC REG LINEAR 1.8V 150MA SC70-5")
      (fields
        (field (name "MANUFACTURER") "Microchip Technology")
        (field (name "MANUFACTURERPARTNUMBER") "MIC5366-1.8YC5-TR")
      )
      (libsource (lib "eagle-import") (part "LDO_FIXED_EN-MIC5365-YC5"))
    )
    (comp (ref "X301")
      (value "171826-4-RA")
      (footprint "eagle-import:171826-4")
      (description "CONN HEADER R/A 4POS 2.5MM")
      (fields
        (field (name "MANUFACTURER") "TE Connectivity AMP Connectors")
        (field (name "MANUFACTURERPARTNUMBER") "171826-4")
        (field (name "CLASS") "CONNECTOR")
        (field (name "LINK") "https://www.digikey.de/product-detail/de/171826-4/A112643-ND")
        (field (name "POPULATED") "TRUE")
        (field (name "ROHSCERTIFICATE") "RoHS-konform")
        (field (name "SOURCE") "DIGIKEY")
        (field (name "SOURCEPARTNUMBER") "A112643-ND")
      )
      (libsource (lib "eagle-import") (part "171826-4-RA"))
    )
    (comp (ref "C201")
      (value "100n")
      (footprint "eagle-import:_0603")
      (description "CAP CER 0.1UF 16V X7R 0603")
      (fields
        (field (name "MANUFACTURER") "Yageo")
        (field (name "MANUFACTURERPARTNUMBER") "CC0603KRX7R7BB104")
      )
      (libsource (lib "eagle-import") (part "CAP_CERAMIC_0603"))
    )
    (comp (ref "C202")
      (value "33p")
      (footprint "eagle-import:_0402")
      (description "CAP CER 33PF 50V NP0 0402")
      (fields
        (field (name "MANUFACTURER") "Samsung Electro-Mechanics America, Inc.")
        (field (name "MANUFACTURERPARTNUMBER") "CL05C330JB5NNNC")
      )
      (libsource (lib "eagle-import") (part "CAP_CERAMIC_0402"))
    )
    (comp (ref "C203")
      (value "100n")
      (footprint "eagle-import:_0402")
      (description "CAP CER 0.1UF 16V X7R 0402")
      (fields
        (field (name "MANUFACTURER") "Samsung Electro-Mechanics")
        (field (name "MANUFACTURERPARTNUMBER") "CL05B104KO5NNWC")
      )
      (libsource (lib "eagle-import") (part "CAP_CERAMIC_0402"))
    )
    (comp (ref "C204")
      (value "2.2u")
      (footprint "eagle-import:_0603")
      (description "CAP CER 2.2UF 10V X5R 0603")
      (fields
        (field (name "MANUFACTURER") "AVX Corporation")
        (field (name "MANUFACTURERPARTNUMBER") "0603ZD225KAT2A")
      )
      (libsource (lib "eagle-import") (part "CAP_CERAMIC_0603"))
    )
    (comp (ref "C205")
      (value "2.2u")
      (footprint "eagle-import:_0603")
      (description "CAP CER 2.2UF 10V X5R 0603")
      (fields
        (field (name "MANUFACTURER") "AVX Corporation")
        (field (name "MANUFACTURERPARTNUMBER") "0603ZD225KAT2A")
      )
      (libsource (lib "eagle-import") (part "CAP_CERAMIC_0603"))
    )
    (comp (ref "C206")
      (value "100n")
      (footprint "eagle-import:_0402")
      (description "CAP CER 0.1UF 16V X7R 0402")
      (fields
        (field (name "MANUFACTURER") "Samsung Electro-Mechanics")
        (field (name "MANUFACTURERPARTNUMBER") "CL05B104KO5NNWC")
      )
      (libsource (lib "eagle-import") (part "CAP_CERAMIC_0402"))
    )
    (comp (ref "C207")
      (value "100n")
      (footprint "eagle-import:_0402")
      (description "CAP CER 0.1UF 16V X7R 0402")
      (fields
        (field (name "MANUFACTURER") "Samsung Electro-Mechanics")
        (field (name "MANUFACTURERPARTNUMBER") "CL05B104KO5NNWC")
      )
      (libsource (lib "eagle-import") (part "CAP_CERAMIC_0402"))
    )
    (comp (ref "C208")
      (value "100n")
      (footprint "eagle-import:_0402")
      (description "CAP CER 0.1UF 16V X7R 0402")
      (fields
        (field (name "MANUFACTURER") "Samsung Electro-Mechanics")
        (field (name "MANUFACTURERPARTNUMBER") "CL05B104KO5NNWC")
      )
      (libsource (lib "eagle-import") (part "CAP_CERAMIC_0402"))
    )
    (comp (ref "C209")
      (value "100n")
      (footprint "eagle-import:_0402")
      (description "CAP CER 0.1UF 16V X7R 0402")
      (fields
        (field (name "MANUFACTURER") "Samsung Electro-Mechanics")
        (field (name "MANUFACTURERPARTNUMBER") "CL05B104KO5NNWC")
      )
      (libsource (lib "eagle-import") (part "CAP_CERAMIC_0402"))
    )
    (comp (ref "C210")
      (value "100n")
      (footprint "eagle-import:_0402")
      (description "CAP CER 0.1UF 16V X7R 0402")
      (fields
        (field (name "MANUFACTURER") "Samsung Electro-Mechanics")
        (field (name "MANUFACTURERPARTNUMBER") "CL05B104KO5NNWC")
      )
      (libsource (lib "eagle-import") (part "CAP_CERAMIC_0402"))
    )
    (comp (ref "C211")
      (value "100n")
      (footprint "eagle-import:_0402")
      (description "CAP CER 0.1UF 16V X7R 0402")
      (fields
        (field (name "MANUFACTURER") "Samsung Electro-Mechanics")
        (field (name "MANUFACTURERPARTNUMBER") "CL05B104KO5NNWC")
      )
      (libsource (lib "eagle-import") (part "CAP_CERAMIC_0402"))
    )
    (comp (ref "C212")
      (value "100n")
      (footprint "eagle-import:_0402")
      (description "CAP CER 0.1UF 16V X7R 0402")
      (fields
        (field (name "MANUFACTURER") "Samsung Electro-Mechanics")
        (field (name "MANUFACTURERPARTNUMBER") "CL05B104KO5NNWC")
      )
      (libsource (lib "eagle-import") (part "CAP_CERAMIC_0402"))
    )
    (comp (ref "C213")
      (value "100n")
      (footprint "eagle-import:_0402")
      (description "CAP CER 0.1UF 16V X7R 0402")
      (fields
        (field (name "MANUFACTURER") "Samsung Electro-Mechanics")
        (field (name "MANUFACTURERPARTNUMBER") "CL05B104KO5NNWC")
      )
      (libsource (lib "eagle-import") (part "CAP_CERAMIC_0402"))
    )
    (comp (ref "C214")
      (value "100n")
      (footprint "eagle-import:_0402")
      (description "CAP CER 0.1UF 16V X7R 0402")
      (fields
        (field (name "MANUFACTURER") "Samsung Electro-Mechanics")
        (field (name "MANUFACTURERPARTNUMBER") "CL05B104KO5NNWC")
      )
      (libsource (lib "eagle-import") (part "CAP_CERAMIC_0402"))
    )
    (comp (ref "C215")
      (value "100n")
      (footprint "eagle-import:_0402")
      (description "CAP CER 0.1UF 16V X7R 0402")
      (fields
        (field (name "MANUFACTURER") "Samsung Electro-Mechanics")
        (field (name "MANUFACTURERPARTNUMBER") "CL05B104KO5NNWC")
      )
      (libsource (lib "eagle-import") (part "CAP_CERAMIC_0402"))
    )
    (comp (ref "C216")
      (value "18p")
      (footprint "eagle-import:_0603")
      (description "CAP CER 18PF 100V 5% NP0 0603")
      (fields
        (field (name "MANUFACTURER") "Murata Electronics North America")
        (field (name "MANUFACTURERPARTNUMBER") "GRM1885C2A180JA01D")
      )
      (libsource (lib "eagle-import") (part "CAP_CERAMIC_0603"))
    )
    (comp (ref "C217")
      (value "18p")
      (footprint "eagle-import:_0603")
      (description "CAP CER 18PF 100V 5% NP0 0603")
      (fields
        (field (name "MANUFACTURER") "Murata Electronics North America")
        (field (name "MANUFACTURERPARTNUMBER") "GRM1885C2A180JA01D")
      )
      (libsource (lib "eagle-import") (part "CAP_CERAMIC_0603"))
    )
    (comp (ref "C218")
      (value "DNP")
      (footprint "eagle-import:_0603")
      (description "CAP CER 1000PF 16V 10% X7R 0402")
      (fields
        (field (name "MANUFACTURER") "Yageo")
        (field (name "MANUFACTURERPARTNUMBER") "CC0402KRX7R7BB102")
      )
      (libsource (lib "eagle-import") (part "CAP_CERAMIC_0603"))
    )
    (comp (ref "C219")
      (value "33p")
      (footprint "eagle-import:_0402")
      (description "CAP CER 33PF 50V NP0 0402")
      (fields
        (field (name "MANUFACTURER") "Samsung Electro-Mechanics America, Inc.")
        (field (name "MANUFACTURERPARTNUMBER") "CL05C330JB5NNNC")
      )
      (libsource (lib "eagle-import") (part "CAP_CERAMIC_0402"))
    )
    (comp (ref "IC201")
      (value "CB3Q3244PW")
      (footprint "eagle-import:TSSOP20")
      (description "IC BUS SWITCH 4 X 1:1 20TSSOP")
      (fields
        (field (name "MANUFACTURERPARTNUMBER") "SN74CB3Q3244PWR")
        (field (name "CLASS") "IC")
        (field (name "LINK") "https://www.digikey.de/product-detail/de/texas-instruments/SN74CB3Q3244PWR/296-17824-1-ND/")
        (field (name "MANUFACTURER") "Texas Instruments")
        (field (name "POPULATED") "TRUE")
        (field (name "ROHSCERTIFICATE") "RoHS3-konform")
        (field (name "SOURCE") "DIGIKEY")
      )
      (libsource (lib "eagle-import") (part "CB3Q3244PW"))
    )
    (comp (ref "IC202")
      (value "CB3Q3244PW")
      (footprint "eagle-import:TSSOP20")
      (description "IC BUS SWITCH 4 X 1:1 20TSSOP")
      (fields
        (field (name "MANUFACTURERPARTNUMBER") "SN74CB3Q3244PWR")
        (field (name "CLASS") "IC")
        (field (name "LINK") "https://www.digikey.de/product-detail/de/texas-instruments/SN74CB3Q3244PWR/296-17824-1-ND/")
        (field (name "MANUFACTURER") "Texas Instruments")
        (field (name "POPULATED") "TRUE")
        (field (name "ROHSCERTIFICATE") "RoHS3-konform")
        (field (name "SOURCE") "DIGIKEY")
      )
      (libsource (lib "eagle-import") (part "CB3Q3244PW"))
    )
    (comp (ref "IC203")
      (value "IP4234CZ6")
      (footprint "eagle-import:TSOP-6")
      (description "TVS DIODE 5.5VWM 6TSOP")
      (fields
        (field (name "MANUFACTURER") "Nexperia USA Inc.")
        (field (name "MANUFACTURERPARTNUMBER") "IP4234CZ6,115")
      )
      (libsource (lib "eagle-import") (part "IP4234CZ6"))
    )
    (comp (ref "IC204")
      (value "FPF2109")
      (footprint "eagle-import:SOT23-5")
      (description "IC PWR SWITCH P-CHAN 1:1 SOT23-5")
      (fields (field (name "MANUFACTURER") "ON Semiconductor"))
      (libsource (lib "eagle-import") (part "FPF21XX"))
    )
    (comp (ref "IC205")
      (value "FPF2109")
      (footprint "eagle-import:SOT23-5")
      (description "IC PWR SWITCH P-CHAN 1:1 SOT23-5")
      (fields (field (name "MANUFACTURER") "ON Semiconductor"))
      (libsource (lib "eagle-import") (part "FPF21XX"))
    )
    (comp (ref "L201")
      (value "744231091")
      (footprint "eagle-import:WE-CNSW_0805")
      (description "CMC 400MA 2LN 90OHM SMD AEC-Q200")
      (fields
        (field (name "MANUFACTURER") "Bourns Inc.")
        (field (name "MANUFACTURERPARTNUMBER") "SRF2012A-900YA")
      )
      (libsource (lib "eagle-import") (part "WE-CNSW_0805"))
    )
    (comp (ref "L202")
      (value "74279220601")
      (footprint "eagle-import:_0805")
      (description "FERRITE BEAD")
      (fields (field (name "MANUFACTURER") "Wurth Electronics Inc"))
      (libsource (lib "eagle-import") (part "INDUCTOR_0805"))
    )
    (comp (ref "LED201")
      (value "LEDPLCC2-MIN-green")
      (footprint "eagle-import:PLCC2-MIN")
      (description "LED GREEN CLEAR 2PLCC SMD")
      (fields
        (field (name "MANUFACTURER") "Broadcom Limited")
        (field (name "MANUFACTURERPARTNUMBER") "HSME-A100-M02J1")
      )
      (libsource (lib "eagle-import") (part "LEDPLCC2-MIN"))
    )
    (comp (ref "LED202")
      (value "KPH-1608EC")
      (footprint "eagle-import:CHIP-LED0603")
      (description "chipLED 0603 red")
      (fields (field (name "MANUFACTURERPARTNUMBER") "UNKNOWN MANUFACTURER PART NUMBER"))
      (libsource (lib "eagle-import") (part "LEDCHIP-LED0603"))
    )
    (comp (ref "Q201")
      (value "12MHz")
      (footprint "eagle-import:HC49UP")
      (description "CRYSTAL 12.0000MHZ 18PF SMD")
      (fields
        (field (name "MANUFACTURER") "Cardinal Components Inc.")
        (field (name "MANUFACTURERPARTNUMBER") "CSM1Z-A5B2C3-40-12.0D18")
      )
      (libsource (lib "eagle-import") (part "CRYSTALHC49UP"))
    )
    (comp (ref "R201")
      (value "330")
      (footprint "eagle-import:_0603")
      (description "RES SMD 330 OHM 1%% 1/10W 0603")
      (fields
        (field (name "MANUFACTURER") "Yageo")
        (field (name "MANUFACTURERPARTNUMBER") "RC0603FR-07330RL")
      )
      (libsource (lib "eagle-import") (part "RESISTOR_0603"))
    )
    (comp (ref "R202")
      (value "100k")
      (footprint "eagle-import:_0603")
      (description "RES 100K OHM 1%% 1/10W 0603")
      (fields
        (field (name "MANUFACTURER") "Stackpole Electronics Inc")
        (field (name "MANUFACTURERPARTNUMBER") "RMCF0603FT100K")
      )
      (libsource (lib "eagle-import") (part "RESISTOR_0603"))
    )
    (comp (ref "R203")
      (value "330")
      (footprint "eagle-import:_0603")
      (description "RES SMD 330 OHM 1%% 1/10W 0603")
      (fields
        (field (name "MANUFACTURER") "Yageo")
        (field (name "MANUFACTURERPARTNUMBER") "RC0603FR-07330RL")
      )
      (libsource (lib "eagle-import") (part "RESISTOR_0603"))
    )
    (comp (ref "R204")
      (value "10k")
      (footprint "eagle-import:_0603")
      (description "RES SMD 10K OHM 1%% 1/10W 0603")
      (fields
        (field (name "MANUFACTURER") "TE Connectivity Passive Product")
        (field (name "MANUFACTURERPARTNUMBER") "CRG0603F10K/10")
      )
      (libsource (lib "eagle-import") (part "RESISTOR_0603"))
    )
    (comp (ref "R205")
      (value "10k")
      (footprint "eagle-import:_0603")
      (description "RES SMD 10K OHM 1%% 1/10W 0603")
      (fields
        (field (name "MANUFACTURER") "TE Connectivity Passive Product")
        (field (name "MANUFACTURERPARTNUMBER") "CRG0603F10K/10")
      )
      (libsource (lib "eagle-import") (part "RESISTOR_0603"))
    )
    (comp (ref "R206")
      (value "27")
      (footprint "eagle-import:_0603")
      (description "RES SMD 27 OHM 5% 1/10W 0603")
      (fields (field (name "MANUFACTURER") "Yageo") (field (name "MANUFACTURERPARTNUMBER") "RC0603JR-0727RL"))
      (libsource (lib "eagle-import") (part "RESISTOR_0603"))
    )
    (comp (ref "R207")
      (value "27")
      (footprint "eagle-import:_0603")
      (description "RES SMD 27 OHM 5% 1/10W 0603")
      (fields (field (name "MANUFACTURER") "Yageo") (field (name "MANUFACTURERPARTNUMBER") "RC0603JR-0727RL"))
      (libsource (lib "eagle-import") (part "RESISTOR_0603"))
    )
    (comp (ref "R208")
      (value "10k")
      (footprint "eagle-import:_0603")
      (description "RES SMD 10K OHM 1%% 1/10W 0603")
      (fields
        (field (name "MANUFACTURER") "TE Connectivity Passive Product")
        (field (name "MANUFACTURERPARTNUMBER") "CRG0603F10K/10")
      )
      (libsource (lib "eagle-import") (part "RESISTOR_0603"))
    )
    (comp (ref "R209")
      (value "1.5k")
      (footprint "eagle-import:_0603")
      (description "CRGCQ 0603 1K5 1%%")
      (fields
        (field (name "MANUFACTURER") "TE Connectivity Passive Product")
        (field (name "MANUFACTURERPARTNUMBER") "CRGCQ0603F1K5")
      )
      (libsource (lib "eagle-import") (part "RESISTOR_0603"))
    )
    (comp (ref "R210")
      (value "47")
      (footprint "eagle-import:_0402")
      (description "RES SMD 47R 0402 1%")
      (fields
        (field (name "MANUFACTURER") "TE Connectivity Passive Product")
        (field (name "MANUFACTURERPARTNUMBER") "CRGCQ0402F47R")
      )
      (libsource (lib "eagle-import") (part "RESISTOR_0402"))
    )
    (comp (ref "R211")
      (value "10k")
      (footprint "eagle-import:_0603")
      (description "RES SMD 10K OHM 1%% 1/10W 0603")
      (fields
        (field (name "MANUFACTURER") "TE Connectivity Passive Product")
        (field (name "MANUFACTURERPARTNUMBER") "CRG0603F10K/10")
      )
      (libsource (lib "eagle-import") (part "RESISTOR_0603"))
    )
    (comp (ref "R212")
      (value "30k")
      (footprint "eagle-import:_0603")
      (description "RES SMD 30K OHM 1%% 1/10W 0603")
      (fields (field (name "MANUFACTURER") "Yageo") (field (name "MANUFACTURERPARTNUMBER") "RC0603FR-0730KL"))
      (libsource (lib "eagle-import") (part "RESISTOR_0603"))
    )
    (comp (ref "R213")
      (value "47k")
      (footprint "eagle-import:_0603")
      (description "RES 47K OHM 1%% 1/10W 0603")
      (fields
        (field (name "MANUFACTURER") "Stackpole Electronics Inc")
        (field (name "MANUFACTURERPARTNUMBER") "RMCF0603FT47K0")
      )
      (libsource (lib "eagle-import") (part "RESISTOR_0603"))
    )
    (comp (ref "R214")
      (value "100k")
      (footprint "eagle-import:_0603")
      (description "RES 100K OHM 1%% 1/10W 0603")
      (fields
        (field (name "MANUFACTURER") "Stackpole Electronics Inc")
        (field (name "MANUFACTURERPARTNUMBER") "RMCF0603FT100K")
      )
      (libsource (lib "eagle-import") (part "RESISTOR_0603"))
    )
    (comp (ref "R215")
      (value "10k")
      (footprint "eagle-import:_0603")
      (description "RES SMD 10K OHM 1%% 1/10W 0603")
      (fields
        (field (name "MANUFACTURER") "TE Connectivity Passive Product")
        (field (name "MANUFACTURERPARTNUMBER") "CRG0603F10K/10")
      )
      (libsource (lib "eagle-import") (part "RESISTOR_0603"))
    )
    (comp (ref "R216")
      (value "10k")
      (footprint "eagle-import:_0603")
      (description "RES SMD 10K OHM 1%% 1/10W 0603")
      (fields
        (field (name "MANUFACTURER") "TE Connectivity Passive Product")
        (field (name "MANUFACTURERPARTNUMBER") "CRG0603F10K/10")
      )
      (libsource (lib "eagle-import") (part "RESISTOR_0603"))
    )
    (comp (ref "R217")
      (value "10k")
      (footprint "eagle-import:_0603")
      (description "RES SMD 10K OHM 1%% 1/10W 0603")
      (fields
        (field (name "MANUFACTURER") "TE Connectivity Passive Product")
        (field (name "MANUFACTURERPARTNUMBER") "CRG0603F10K/10")
      )
      (libsource (lib "eagle-import") (part "RESISTOR_0603"))
    )
    (comp (ref "R218")
      (value "10k")
      (footprint "eagle-import:_0603")
      (description "RES SMD 10K OHM 1%% 1/10W 0603")
      (fields
        (field (name "MANUFACTURER") "TE Connectivity Passive Product")
        (field (name "MANUFACTURERPARTNUMBER") "CRG0603F10K/10")
      )
      (libsource (lib "eagle-import") (part "RESISTOR_0603"))
    )
    (comp (ref "R219")
      (value "100k")
      (footprint "eagle-import:_0603")
      (description "RES 100K OHM 1%% 1/10W 0603")
      (fields
        (field (name "MANUFACTURER") "Stackpole Electronics Inc")
        (field (name "MANUFACTURERPARTNUMBER") "RMCF0603FT100K")
      )
      (libsource (lib "eagle-import") (part "RESISTOR_0603"))
    )
    (comp (ref "R220")
      (value "DNP")
      (footprint "eagle-import:_0603")
      (description "NO DESCRIPTION")
      (fields
        (field (name "MANUFACTURER") "UNKNOWN MANUFACTURER")
        (field (name "MANUFACTURERPARTNUMBER") "UNKNOWN MANUFACTURER PART NUMBER")
      )
      (libsource (lib "eagle-import") (part "RESISTOR_0603"))
    )
    (comp (ref "R221")
      (value "DNP")
      (footprint "eagle-import:_0603")
      (description "NO DESCRIPTION")
      (fields
        (field (name "MANUFACTURER") "UNKNOWN MANUFACTURER")
        (field (name "MANUFACTURERPARTNUMBER") "UNKNOWN MANUFACTURER PART NUMBER")
      )
      (libsource (lib "eagle-import") (part "RESISTOR_0603"))
    )
    (comp (ref "TC201")
      (value "TC2050-IDC")
      (footprint "eagle-import:TC2050-IDC")
      (description "TAG-CONNECT footprint")
      (fields (field (name "MANUFACTURER") "TAG-CONNECT") (field (name "MANUFACTURERPARTNUMBER") "TC-2050"))
      (libsource (lib "eagle-import") (part "TC2050-IDC"))
    )
    (comp (ref "TP1")
      (value "TPTP14R")
      (footprint "eagle-import:TP14R")
      (description "NO DESCRIPTION")
      (fields
        (field (name "MANUFACTURER") "UNKNOWN MANUFACTURER")
        (field (name "MANUFACTURERPARTNUMBER") "UNKNOWN MANUFACTURER PART NUMBER")
      )
      (libsource (lib "eagle-import") (part "TPTP14R"))
    )
    (comp (ref "TP2")
      (value "TPTP14R")
      (footprint "eagle-import:TP14R")
      (description "NO DESCRIPTION")
      (fields
        (field (name "MANUFACTURER") "UNKNOWN MANUFACTURER")
        (field (name "MANUFACTURERPARTNUMBER") "UNKNOWN MANUFACTURER PART NUMBER")
      )
      (libsource (lib "eagle-import") (part "TPTP14R"))
    )
    (comp (ref "U201")
      (value "IP4234CZ6")
      (footprint "eagle-import:TSOP-6")
      (description "TVS DIODE 5.5VWM 6TSOP")
      (fields
        (field (name "MANUFACTURER") "Nexperia USA Inc.")
        (field (name "MANUFACTURERPARTNUMBER") "IP4234CZ6,115")
      )
      (libsource (lib "eagle-import") (part "IP4234CZ6"))
    )
    (comp (ref "U202")
      (value "AT91SAM3S-AU")
      (footprint "eagle-import:LQFP64")
      (description "IC MCU 32BIT 256KB FLASH 64LQFP")
      (fields (field (name "MANUFACTURER") "Atmel") (field (name "MANUFACTURERPARTNUMBER") "ATSAM3S4BA-AU"))
      (libsource (lib "eagle-import") (part "AT91SAM3S-AU"))
    )
    (comp (ref "X201")
      (value "MINI-USB-SHIELD-UX60-MB-5ST")
      (footprint "eagle-import:UX60-MB-5ST")
      (fields
        (field (name "CLASS") "CONNECTOR")
        (field (name "LINK") "http://www.digikey.com/product-detail/en/hirose-electric-co-ltd/UX60-MB-5ST/H2959CT-ND/597538")
        (field (name "POPULATED") "TRUE")
        (field (name "SOURCE") "DIGIKEY")
      )
      (libsource (lib "eagle-import") (part "MINI-USB-SHIELD-UX60-MB-5ST"))
    )
    (comp (ref "X202")
      (value "2.54mm")
      (footprint "eagle-import:1X03_LOCK")
      (description "NO DESCRIPTION")
      (fields
        (field (name "MANUFACTURER") "UNKNOWN MANUFACTURER")
        (field (name "MANUFACTURERPARTNUMBER") "UNKNOWN MANUFACTURER PART NUMBER")
      )
      (libsource (lib "eagle-import") (part "PINHD-1X3LOCK"))
    )
    (comp (ref "X203")
      (value "JACK2.5_SJ-2523")
      (footprint "eagle-import:JACK2.5_SJ-2523")
      (description "CONN JACK STEREO 2.5MM SMD R/A")
      (fields
        (field (name "MANUFACTURER") "CUI Inc.")
        (field (name "MANUFACTURERPARTNUMBER") "SJ-2523-SMT-TR")
      )
      (libsource (lib "eagle-import") (part "JACK2.5_SJ-2523"))
    )
  )
  (nets
    (net (code "1") (name "+VIN") (class "Default")
      (node (ref "D301") (pin "A") (pinfunction "A_A") (pintype "passive"))
      (node (ref "J301") (pin "1") (pinfunction "1_1") (pintype "passive"))
      (node (ref "J301") (pin "1-1") (pinfunction "1_1-1") (pintype "passive"))
      (node (ref "R301") (pin "2") (pinfunction "2_2") (pintype "passive"))
      (node (ref "R302") (pin "1") (pinfunction "1_1") (pintype "passive"))
    )
    (net (code "2") (name "+VIN_PROT") (class "Default")
      (node (ref "C301") (pin "+") (pinfunction "+_+") (pintype "passive"))
      (node (ref "C302") (pin "1") (pinfunction "1_1") (pintype "passive"))
      (node (ref "C303") (pin "2") (pinfunction "2_2") (pintype "passive"))
      (node (ref "C313") (pin "+") (pinfunction "+_+") (pintype "passive"))
      (node (ref "D301") (pin "C") (pinfunction "C_C") (pintype "passive"))
      (node (ref "D302") (pin "C") (pinfunction "C_C") (pintype "passive"))
      (node (ref "DCDC301") (pin "2") (pinfunction "VIN_2") (pintype "passive"))
      (node (ref "R309") (pin "1") (pinfunction "1_1") (pintype "passive"))
    )
    (net (code "3") (name "EN_MDM_SIM_VDD") (class "Default")
      (node (ref "IC205") (pin "3") (pinfunction "EN_3") (pintype "input"))
      (node (ref "R217") (pin "1") (pinfunction "1_1") (pintype "passive"))
      (node (ref "U202") (pin "19") (pinfunction "PWML2/TIOB1/TK/PA16_19") (pintype "bidirectional"))
    )
    (net (code "4") (name "EN_ST_SIM_VDD") (class "Default")
      (node (ref "IC204") (pin "3") (pinfunction "EN_3") (pintype "input"))
      (node (ref "R216") (pin "1") (pinfunction "1_1") (pintype "passive"))
      (node (ref "U202") (pin "5") (pinfunction "URXD1/AD6/PB2_5") (pintype "bidirectional"))
    )
    (net (code "5") (name "ERASE") (class "Default")
      (node (ref "R208") (pin "2") (pinfunction "2_2") (pintype "passive"))
      (node (ref "TP1") (pin "TP") (pinfunction "TP_TP") (pintype "input"))
      (node (ref "U202") (pin "55") (pinfunction "PB12/ERASE_55") (pintype "bidirectional"))
    )
    (net (code "6") (name "GND") (class "Default")
      (node (ref "C101") (pin "2") (pinfunction "2_2") (pintype "passive"))
      (node (ref "C102") (pin "2") (pinfunction "2_2") (pintype "passive"))
      (node (ref "C103") (pin "2") (pinfunction "2_2") (pintype "passive"))
      (node (ref "C104") (pin "2") (pinfunction "2_2") (pintype "passive"))
      (node (ref "C105") (pin "2") (pinfunction "2_2") (pintype "passive"))
      (node (ref "C106") (pin "2") (pinfunction "2_2") (pintype "passive"))
      (node (ref "C107") (pin "1") (pinfunction "1_1") (pintype "passive"))
      (node (ref "C108") (pin "1") (pinfunction "1_1") (pintype "passive"))
      (node (ref "C109") (pin "1") (pinfunction "1_1") (pintype "passive"))
      (node (ref "C110") (pin "2") (pinfunction "2_2") (pintype "passive"))
      (node (ref "C111") (pin "2") (pinfunction "2_2") (pintype "passive"))
      (node (ref "C112") (pin "1") (pinfunction "1_1") (pintype "passive"))
      (node (ref "C113") (pin "1") (pinfunction "1_1") (pintype "passive"))
      (node (ref "C114") (pin "1") (pinfunction "1_1") (pintype "passive"))
      (node (ref "C115") (pin "2") (pinfunction "2_2") (pintype "passive"))
      (node (ref "C116") (pin "2") (pinfunction "2_2") (pintype "passive"))
      (node (ref "C117") (pin "1") (pinfunction "1_1") (pintype "passive"))
      (node (ref "C201") (pin "1") (pinfunction "1_1") (pintype "passive"))
      (node (ref "C203") (pin "1") (pinfunction "1_1") (pintype "passive"))
      (node (ref "C204") (pin "1") (pinfunction "1_1") (pintype "passive"))
      (node (ref "C205") (pin "1") (pinfunction "1_1") (pintype "passive"))
      (node (ref "C206") (pin "1") (pinfunction "1_1") (pintype "passive"))
      (node (ref "C207") (pin "1") (pinfunction "1_1") (pintype "passive"))
      (node (ref "C208") (pin "1") (pinfunction "1_1") (pintype "passive"))
      (node (ref "C209") (pin "1") (pinfunction "1_1") (pintype "passive"))
      (node (ref "C210") (pin "1") (pinfunction "1_1") (pintype "passive"))
      (node (ref "C211") (pin "1") (pinfunction "1_1") (pintype "passive"))
      (node (ref "C212") (pin "1") (pinfunction "1_1") (pintype "passive"))
      (node (ref "C213") (pin "1") (pinfunction "1_1") (pintype "passive"))
      (node (ref "C214") (pin "1") (pinfunction "1_1") (pintype "passive"))
      (node (ref "C215") (pin "1") (pinfunction "1_1") (pintype "passive"))
      (node (ref "C216") (pin "2") (pinfunction "2_2") (pintype "passive"))
      (node (ref "C217") (pin "2") (pinfunction "2_2") (pintype "passive"))
      (node (ref "C218") (pin "2") (pinfunction "2_2") (pintype "passive"))
      (node (ref "C219") (pin "2") (pinfunction "2_2") (pintype "passive"))
      (node (ref "C301") (pin "-") (pinfunction "-_-") (pintype "passive"))
      (node (ref "C302") (pin "2") (pinfunction "2_2") (pintype "passive"))
      (node (ref "C303") (pin "1") (pinfunction "1_1") (pintype "passive"))
      (node (ref "C304") (pin "1") (pinfunction "1_1") (pintype "passive"))
      (node (ref "C305") (pin "1") (pinfunction "1_1") (pintype "passive"))
      (node (ref "C306") (pin "1") (pinfunction "1_1") (pintype "passive"))
      (node (ref "C307") (pin "2") (pinfunction "2_2") (pintype "passive"))
      (node (ref "C308") (pin "1") (pinfunction "1_1") (pintype "passive"))
      (node (ref "C309") (pin "-") (pinfunction "-_-") (pintype "passive"))
      (node (ref "C310") (pin "2") (pinfunction "2_2") (pintype "bidirectional"))
      (node (ref "C311") (pin "1") (pinfunction "1_1") (pintype "passive"))
      (node (ref "C313") (pin "-") (pinfunction "-_-") (pintype "passive"))
      (node (ref "D101") (pin "2") (pinfunction "GND_2") (pintype "passive"))
      (node (ref "D102") (pin "10") (pinfunction "GND_10") (pintype "passive"))
      (node (ref "D302") (pin "A") (pinfunction "A_A") (pintype "passive"))
      (node (ref "DCDC301") (pin "3") (pinfunction "GND_3") (pintype "passive"))
      (node (ref "DCDC301") (pin "7") (pinfunction "GND_7") (pintype "passive"))
      (node (ref "H301") (pin "B3,2") (pinfunction "MOUNT_B3,2") (pintype "passive"))
      (node (ref "H302") (pin "B3,2") (pinfunction "MOUNT_B3,2") (pintype "passive"))
      (node (ref "H303") (pin "B3,2") (pinfunction "MOUNT_B3,2") (pintype "passive"))
      (node (ref "H304") (pin "B3,2") (pinfunction "MOUNT_B3,2") (pintype "passive"))
      (node (ref "IC201") (pin "10") (pinfunction "GND_10") (pintype "passive"))
      (node (ref "IC202") (pin "10") (pinfunction "GND_10") (pintype "passive"))
      (node (ref "IC203") (pin "2") (pinfunction "GND_2") (pintype "passive"))
      (node (ref "IC204") (pin "2") (pinfunction "GND_2") (pintype "passive"))
      (node (ref "IC205") (pin "2") (pinfunction "GND_2") (pintype "passive"))
      (node (ref "IC301") (pin "6") (pinfunction "GND_6") (pintype "power_in"))
      (node (ref "IC301") (pin "EXP") (pinfunction "GND_EXP") (pintype "power_in"))
      (node (ref "IC302") (pin "6") (pinfunction "GND_6") (pintype "power_in"))
      (node (ref "J301") (pin "2") (pinfunction "2_2") (pintype "passive"))
      (node (ref "J301") (pin "3") (pinfunction "3_3") (pintype "passive"))
      (node (ref "LED102") (pin "K") (pinfunction "C_K") (pintype "passive"))
      (node (ref "NGFF101") (pin "11") (pinfunction "GND_11") (pintype "power_in"))
      (node (ref "NGFF101") (pin "27") (pinfunction "GND_27") (pintype "power_in"))
      (node (ref "NGFF101") (pin "3") (pinfunction "GND_3") (pintype "power_in"))
      (node (ref "NGFF101") (pin "33") (pinfunction "GND_33") (pintype "power_in"))
      (node (ref "NGFF101") (pin "39") (pinfunction "GND_39") (pintype "power_in"))
      (node (ref "NGFF101") (pin "45") (pinfunction "GND_45") (pintype "power_in"))
      (node (ref "NGFF101") (pin "5") (pinfunction "GND_5") (pintype "power_in"))
      (node (ref "NGFF101") (pin "51") (pinfunction "GND_51") (pintype "power_in"))
      (node (ref "NGFF101") (pin "57") (pinfunction "GND_57") (pintype "power_in"))
      (node (ref "NGFF101") (pin "71") (pinfunction "GND_71") (pintype "power_in"))
      (node (ref "NGFF101") (pin "73") (pinfunction "GND_73") (pintype "power_in"))
      (node (ref "NGFF101") (pin "P$1") (pinfunction "GND_P$1") (pintype "power_in"))
      (node (ref "NGFF101") (pin "P$2") (pinfunction "GND_P$2") (pintype "power_in"))
      (node (ref "R101") (pin "2") (pinfunction "2_2") (pintype "passive"))
      (node (ref "R102") (pin "2") (pinfunction "2_2") (pintype "passive"))
      (node (ref "R112") (pin "1") (pinfunction "1_1") (pintype "passive"))
      (node (ref "R114") (pin "1") (pinfunction "1_1") (pintype "passive"))
      (node (ref "R121") (pin "1") (pinfunction "1_1") (pintype "passive"))
      (node (ref "R202") (pin "2") (pinfunction "2_2") (pintype "passive"))
      (node (ref "R205") (pin "2") (pinfunction "2_2") (pintype "passive"))
      (node (ref "R208") (pin "1") (pinfunction "1_1") (pintype "passive"))
      (node (ref "R213") (pin "1") (pinfunction "1_1") (pintype "passive"))
      (node (ref "R216") (pin "2") (pinfunction "2_2") (pintype "passive"))
      (node (ref "R219") (pin "1") (pinfunction "1_1") (pintype "passive"))
      (node (ref "R303") (pin "1") (pinfunction "1_1") (pintype "passive"))
      (node (ref "R305") (pin "1") (pinfunction "1_1") (pintype "passive"))
      (node (ref "R308") (pin "2") (pinfunction "2_2") (pintype "passive"))
      (node (ref "R310") (pin "2") (pinfunction "2_2") (pintype "passive"))
      (node (ref "SIM101") (pin "C5") (pinfunction "GND_C5") (pintype "passive"))
      (node (ref "SIM101") (pin "S1") (pinfunction "SHLD_S1") (pintype "passive"))
      (node (ref "SIM101") (pin "S2") (pinfunction "SHLD_S2") (pintype "passive"))
      (node (ref "T101") (pin "E") (pinfunction "E_E") (pintype "passive"))
      (node (ref "T102") (pin "E") (pinfunction "E_E") (pintype "passive"))
      (node (ref "TC201") (pin "10") (pinfunction "10_10") (pintype "passive"))
      (node (ref "TC201") (pin "2") (pinfunction "2_2") (pintype "passive"))
      (node (ref "U201") (pin "2") (pinfunction "GND_2") (pintype "passive"))
      (node (ref "U202") (pin "17") (pinfunction "GND_17") (pintype "power_in"))
      (node (ref "U202") (pin "2") (pinfunction "GND_2") (pintype "power_in"))
      (node (ref "U202") (pin "3") (pinfunction "PWMH0/AD4/PB0_3") (pintype "bidirectional"))
      (node (ref "U202") (pin "4") (pinfunction "PWMH1/AD5/PB1_4") (pintype "bidirectional"))
      (node (ref "U202") (pin "46") (pinfunction "GND_46") (pintype "power_in"))
      (node (ref "U202") (pin "50") (pinfunction "JTAGSEL_50") (pintype "bidirectional"))
      (node (ref "U202") (pin "60") (pinfunction "GND_60") (pintype "power_in"))
      (node (ref "U301") (pin "2") (pinfunction "GND_2") (pintype "power_in"))
      (node (ref "X101") (pin "6") (pinfunction "6_6") (pintype "passive"))
      (node (ref "X102") (pin "5") (pinfunction "GND_5") (pintype "passive"))
      (node (ref "X102") (pin "8") (pinfunction "GND_8") (pintype "passive"))
      (node (ref "X103") (pin "1") (pinfunction "1_1") (pintype "passive"))
      (node (ref "X103") (pin "3") (pinfunction "3_3") (pintype "passive"))
      (node (ref "X103") (pin "5") (pinfunction "5_5") (pintype "passive"))
      (node (ref "X201") (pin "5") (pinfunction "5_5") (pintype "input"))
      (node (ref "X202") (pin "3") (pinfunction "3_3") (pintype "passive"))
      (node (ref "X203") (pin "1") (pinfunction "RING_1") (pintype "passive"))
      (node (ref "X301") (pin "2") (pinfunction "S_2") (pintype "passive"))
      (node (ref "X301") (pin "3") (pinfunction "S_3") (pintype "passive"))
    )
    (net (code "7") (name "MDM_SIM_DET") (class "Default")
      (node (ref "IC201") (pin "12") (pinfunction "B_12") (pintype "bidirectional"))
      (node (ref "IC201") (pin "17") (pinfunction "A_17") (pintype "bidirectional"))
      (node (ref "NGFF101") (pin "66") (pinfunction "SIM_DET_66") (pintype "input"))
    )
    (net (code "8") (name "MDM_UIM_CLK") (class "Default")
      (node (ref "IC201") (pin "13") (pinfunction "A_13") (pintype "bidirectional"))
      (node (ref "IC201") (pin "16") (pinfunction "B_16") (pintype "bidirectional"))
      (node (ref "R117") (pin "2") (pinfunction "2_2") (pintype "passive"))
    )
    (net (code "9") (name "MDM_UIM_IO") (class "Default")
      (node (ref "IC201") (pin "11") (pinfunction "A_11") (pintype "bidirectional"))
      (node (ref "IC201") (pin "18") (pinfunction "B_18") (pintype "bidirectional"))
      (node (ref "R119") (pin "2") (pinfunction "2_2") (pintype "passive"))
    )
    (net (code "10") (name "MDM_UIM_VDD") (class "Default")
      (node (ref "IC205") (pin "1") (pinfunction "IN_1") (pintype "passive"))
      (node (ref "NGFF101") (pin "36") (pinfunction "UIM_PWR_36") (pintype "power_in"))
      (node (ref "R212") (pin "2") (pinfunction "2_2") (pintype "passive"))
    )
    (net (code "11") (name "MODEM_EN") (class "Default")
      (node (ref "IC301") (pin "2") (pinfunction "ON_2") (pintype "input"))
      (node (ref "IC302") (pin "2") (pinfunction "ON_2") (pintype "input"))
      (node (ref "R303") (pin "2") (pinfunction "2_2") (pintype "passive"))
      (node (ref "R311") (pin "1") (pinfunction "1_1") (pintype "passive"))
      (node (ref "U202") (pin "28") (pinfunction "PWMH0/NPCS0/PA11_28") (pintype "bidirectional"))
    )
    (net (code "12") (name "NGFF_USB_VBUS") (class "Default")
      (node (ref "R120") (pin "2") (pinfunction "2_2") (pintype "passive"))
      (node (ref "X102") (pin "1") (pinfunction "VBUS_1") (pintype "passive"))
    )
    (net (code "13") (name "Net-(C117-Pad2)") (class "Default")
      (node (ref "C117") (pin "2") (pinfunction "2_2") (pintype "passive"))
      (node (ref "R121") (pin "2") (pinfunction "2_2") (pintype "passive"))
      (node (ref "X102") (pin "S1") (pinfunction "S1_S1") (pintype "passive"))
      (node (ref "X102") (pin "S2") (pinfunction "S1_S2") (pintype "passive"))
      (node (ref "X102") (pin "S3") (pinfunction "S1_S3") (pintype "passive"))
      (node (ref "X102") (pin "S4") (pinfunction "S1_S4") (pintype "passive"))
      (node (ref "X102") (pin "S5") (pinfunction "S1_S5") (pintype "passive"))
      (node (ref "X102") (pin "S6") (pinfunction "S1_S6") (pintype "passive"))
      (node (ref "X102") (pin "S7") (pinfunction "S1_S7") (pintype "passive"))
      (node (ref "X102") (pin "S8") (pinfunction "S1_S8") (pintype "passive"))
    )
    (net (code "14") (name "Net-(C202-Pad1)") (class "Default")
      (node (ref "C202") (pin "1") (pinfunction "1_1") (pintype "passive"))
      (node (ref "L201") (pin "4") (pinfunction "4_4") (pintype "bidirectional"))
      (node (ref "R206") (pin "1") (pinfunction "1_1") (pintype "passive"))
    )
    (net (code "15") (name "Net-(C202-Pad2)") (class "Default")
      (node (ref "C202") (pin "2") (pinfunction "2_2") (pintype "passive"))
      (node (ref "L201") (pin "1") (pinfunction "1_1") (pintype "bidirectional"))
      (node (ref "R207") (pin "1") (pinfunction "1_1") (pintype "passive"))
    )
    (net (code "16") (name "Net-(C312-Pad2)") (class "Default")
      (node (ref "C312") (pin "2") (pinfunction "2_2") (pintype "passive"))
      (node (ref "R306") (pin "2") (pinfunction "2_2") (pintype "passive"))
    )
    (net (code "17") (name "Net-(DCDC301-ON{slash}OFF)") (class "Default")
      (node (ref "DCDC301") (pin "1") (pinfunction "ON/OFF_1") (pintype "input"))
      (node (ref "R309") (pin "2") (pinfunction "2_2") (pintype "passive"))
      (node (ref "R310") (pin "1") (pinfunction "1_1") (pintype "passive"))
    )
    (net (code "18") (name "Net-(DCDC301-PGOOD)") (class "Default")
      (node (ref "DCDC301") (pin "10") (pinfunction "PGOOD_10") (pintype "output"))
      (node (ref "R304") (pin "2") (pinfunction "2_2") (pintype "passive"))
    )
    (net (code "19") (name "Net-(IC201H-B)") (class "Default")
      (node (ref "IC201") (pin "3") (pinfunction "B_3") (pintype "bidirectional"))
      (node (ref "IC202") (pin "18") (pinfunction "B_18") (pintype "bidirectional"))
    )
    (net (code "20") (name "Net-(IC203-1A)") (class "Default")
      (node (ref "IC203") (pin "1") (pinfunction "1A_1") (pintype "passive"))
      (node (ref "X202") (pin "2") (pinfunction "2_2") (pintype "passive"))
      (node (ref "X203") (pin "3") (pinfunction "MIDDLE_3") (pintype "passive"))
    )
    (net (code "21") (name "Net-(IC203-2A)") (class "Default")
      (node (ref "IC203") (pin "6") (pinfunction "2A_6") (pintype "passive"))
      (node (ref "X202") (pin "1") (pinfunction "1_1") (pintype "passive"))
      (node (ref "X203") (pin "2") (pinfunction "TIP_2") (pintype "passive"))
    )
    (net (code "22") (name "Net-(IC301-CT)") (class "Default")
      (node (ref "C304") (pin "2") (pinfunction "2_2") (pintype "passive"))
      (node (ref "IC301") (pin "7") (pinfunction "CT_7") (pintype "passive"))
    )
    (net (code "23") (name "Net-(IC302-CT)") (class "Default")
      (node (ref "C305") (pin "2") (pinfunction "2_2") (pintype "passive"))
      (node (ref "IC302") (pin "7") (pinfunction "CT_7") (pintype "passive"))
    )
    (net (code "24") (name "Net-(LED101-C)") (class "Default")
      (node (ref "LED101") (pin "K") (pinfunction "C_K") (pintype "passive"))
      (node (ref "R107") (pin "1") (pinfunction "1_1") (pintype "passive"))
    )
    (net (code "25") (name "Net-(LED102-PadA)") (class "Default")
      (node (ref "LED102") (pin "A") (pinfunction "A_A") (pintype "passive"))
      (node (ref "R120") (pin "1") (pinfunction "1_1") (pintype "passive"))
    )
    (net (code "26") (name "Net-(LED201-PadA)") (class "Default")
      (node (ref "LED201") (pin "A") (pinfunction "A_A") (pintype "passive"))
      (node (ref "R201") (pin "1") (pinfunction "1_1") (pintype "passive"))
    )
    (net (code "27") (name "Net-(LED202-PadA)") (class "Default")
      (node (ref "LED202") (pin "A") (pinfunction "A_A") (pintype "passive"))
      (node (ref "R203") (pin "2") (pinfunction "2_2") (pintype "passive"))
    )
    (net (code "28") (name "Net-(LED301-C)") (class "Default")
      (node (ref "LED301") (pin "K") (pinfunction "C_K") (pintype "passive"))
      (node (ref "R305") (pin "2") (pinfunction "2_2") (pintype "passive"))
    )
    (net (code "29") (name "Net-(NGFF101A-~{BODY_SAR})") (class "Default")
      (node (ref "NGFF101") (pin "25") (pinfunction "~{BODY_SAR}_25") (pintype "input"))
      (node (ref "R109") (pin "1") (pinfunction "1_1") (pintype "passive"))
    )
    (net (code "30") (name "Net-(R103-Pad1)") (class "Default")
      (node (ref "R103") (pin "1") (pinfunction "1_1") (pintype "passive"))
      (node (ref "T101") (pin "B") (pinfunction "B_B") (pintype "passive"))
    )
    (net (code "31") (name "Net-(R104-Pad1)") (class "Default")
      (node (ref "R104") (pin "1") (pinfunction "1_1") (pintype "passive"))
      (node (ref "T102") (pin "B") (pinfunction "B_B") (pintype "passive"))
    )
    (net (code "32") (name "Net-(R307-Pad2)") (class "Default")
      (node (ref "R307") (pin "2") (pinfunction "2_2") (pintype "passive"))
      (node (ref "R308") (pin "1") (pinfunction "1_1") (pintype "passive"))
    )
    (net (code "33") (name "Net-(SIM101A-1)") (class "Default")
      (node (ref "R113") (pin "2") (pinfunction "2_2") (pintype "passive"))
      (node (ref "SIM101") (pin "CD2") (pinfunction "1_CD2") (pintype "passive"))
    )
    (net (code "34") (name "Net-(U201-1A)") (class "Default")
      (node (ref "U201") (pin "1") (pinfunction "1A_1") (pintype "passive"))
      (node (ref "X201") (pin "3") (pinfunction "3_3") (pintype "input"))
    )
    (net (code "35") (name "Net-(U201-1B)") (class "Default")
      (node (ref "L201") (pin "2") (pinfunction "2_2") (pintype "bidirectional"))
      (node (ref "U201") (pin "3") (pinfunction "1B_3") (pintype "passive"))
    )
    (net (code "36") (name "Net-(U201-2A)") (class "Default")
      (node (ref "U201") (pin "6") (pinfunction "2A_6") (pintype "passive"))
      (node (ref "X201") (pin "2") (pinfunction "2_2") (pintype "input"))
    )
    (net (code "37") (name "Net-(U201-2B)") (class "Default")
      (node (ref "L201") (pin "3") (pinfunction "3_3") (pintype "bidirectional"))
      (node (ref "U201") (pin "4") (pinfunction "2B_4") (pintype "passive"))
    )
    (net (code "38") (name "Net-(U202-ADVREF)") (class "Default")
      (node (ref "C212") (pin "2") (pinfunction "2_2") (pintype "passive"))
      (node (ref "L202") (pin "2") (pinfunction "2_2") (pintype "passive"))
      (node (ref "U202") (pin "1") (pinfunction "ADVREF_1") (pintype "bidirectional"))
    )
    (net (code "39") (name "Net-(U202-DDM{slash}PB10)") (class "Default")
      (node (ref "R206") (pin "2") (pinfunction "2_2") (pintype "passive"))
      (node (ref "U202") (pin "56") (pinfunction "DDM/PB10_56") (pintype "bidirectional"))
    )
    (net (code "40") (name "Net-(U202-DDP{slash}PB11)") (class "Default")
      (node (ref "R207") (pin "2") (pinfunction "2_2") (pintype "passive"))
      (node (ref "U202") (pin "57") (pinfunction "DDP/PB11_57") (pintype "bidirectional"))
    )
    (net (code "41") (name "Net-(U202-NPCS1{slash}URXD0{slash}PA9)") (class "Default")
      (node (ref "R210") (pin "1") (pinfunction "1_1") (pintype "passive"))
      (node (ref "U202") (pin "30") (pinfunction "NPCS1/URXD0/PA9_30") (pintype "bidirectional"))
    )
    (net (code "42") (name "Net-(U202-PWML3{slash}TIOA1{slash}TF{slash}PA15)") (class "Default")
      (node (ref "R211") (pin "2") (pinfunction "2_2") (pintype "passive"))
      (node (ref "U202") (pin "20") (pinfunction "PWML3/TIOA1/TF/PA15_20") (pintype "bidirectional"))
    )
    (net (code "43") (name "Net-(U202-UTXD1{slash}AD7{slash}PB3)") (class "Default")
      (node (ref "C218") (pin "1") (pinfunction "1_1") (pintype "passive"))
      (node (ref "R212") (pin "1") (pinfunction "1_1") (pintype "passive"))
      (node (ref "R213") (pin "2") (pinfunction "2_2") (pintype "passive"))
      (node (ref "U202") (pin "6") (pinfunction "UTXD1/AD7/PB3_6") (pintype "bidirectional"))
    )
    (net (code "44") (name "Net-(U202-XIN{slash}PGMCK{slash}PB9)") (class "Default")
      (node (ref "C216") (pin "1") (pinfunction "1_1") (pintype "passive"))
      (node (ref "Q201") (pin "2") (pinfunction "2_2") (pintype "passive"))
      (node (ref "U202") (pin "62") (pinfunction "XIN/PGMCK/PB9_62") (pintype "bidirectional"))
    )
    (net (code "45") (name "Net-(U202-XOUT{slash}PB8)") (class "Default")
      (node (ref "C217") (pin "1") (pinfunction "1_1") (pintype "passive"))
      (node (ref "Q201") (pin "1") (pinfunction "1_1") (pintype "passive"))
      (node (ref "U202") (pin "61") (pinfunction "XOUT/PB8_61") (pintype "bidirectional"))
    )
    (net (code "46") (name "Net-(X201B-S1)") (class "Default")
      (node (ref "C201") (pin "2") (pinfunction "2_2") (pintype "passive"))
      (node (ref "R202") (pin "1") (pinfunction "1_1") (pintype "passive"))
      (node (ref "X201") (pin "M1") (pinfunction "S1_M1") (pintype "passive"))
      (node (ref "X201") (pin "M4") (pinfunction "S4_M4") (pintype "passive"))
    )
    (net (code "47") (name "Net-(X301A-S)") (class "Default")
      (node (ref "R302") (pin "2") (pinfunction "2_2") (pintype "passive"))
      (node (ref "X301") (pin "1") (pinfunction "S_1") (pintype "passive"))
    )
    (net (code "48") (name "Net-(X301D-S)") (class "Default")
      (node (ref "R301") (pin "1") (pinfunction "1_1") (pintype "passive"))
      (node (ref "X301") (pin "4") (pinfunction "S_4") (pintype "passive"))
    )
    (net (code "49") (name "PCM_CLK") (class "Default")
      (node (ref "NGFF101") (pin "20") (pinfunction "PCM_CLK/I2S_CLK_20") (pintype "bidirectional"))
      (node (ref "X101") (pin "1") (pinfunction "1_1") (pintype "passive"))
    )
    (net (code "50") (name "PCM_DIN") (class "Default")
      (node (ref "NGFF101") (pin "22") (pinfunction "PCM_DIN/I2S_DIN_22") (pintype "input"))
      (node (ref "X101") (pin "3") (pinfunction "3_3") (pintype "passive"))
    )
    (net (code "51") (name "PCM_DOUT") (class "Default")
      (node (ref "NGFF101") (pin "24") (pinfunction "PCM_DOUT/I2S_DOUT_24") (pintype "output"))
      (node (ref "X101") (pin "2") (pinfunction "2_2") (pintype "passive"))
    )
    (net (code "52") (name "PCM_SYNC") (class "Default")
      (node (ref "NGFF101") (pin "28") (pinfunction "PCM_SYNC/I2S_WS_28") (pintype "bidirectional"))
      (node (ref "X101") (pin "4") (pinfunction "4_4") (pintype "passive"))
    )
    (net (code "53") (name "PERST") (class "Default")
      (node (ref "R102") (pin "1") (pinfunction "1_1") (pintype "passive"))
      (node (ref "R104") (pin "2") (pinfunction "2_2") (pintype "passive"))
      (node (ref "U202") (pin "25") (pinfunction "A23/PWMH2/CTS1/PA25_25") (pintype "bidirectional"))
    )
    (net (code "54") (name "PWR_ON") (class "Default")
      (node (ref "C101") (pin "1") (pinfunction "1_1") (pintype "passive"))
      (node (ref "NGFF101") (pin "6") (pinfunction "PWR_ON_OFF_6") (pintype "input"))
      (node (ref "R111") (pin "2") (pinfunction "2_2") (pintype "passive"))
      (node (ref "R112") (pin "2") (pinfunction "2_2") (pintype "passive"))
      (node (ref "T101") (pin "C") (pinfunction "C_C") (pintype "passive"))
    )
    (net (code "55") (name "SCL") (class "Default")
      (node (ref "U202") (pin "52") (pinfunction "PCK2/NPCS1/PA31_52") (pintype "bidirectional"))
    )
    (net (code "56") (name "SDA") (class "Default")
      (node (ref "U202") (pin "42") (pinfunction "PWML2/NPCS2/PA30_42") (pintype "bidirectional"))
    )
    (net (code "57") (name "SENSE") (class "Default")
      (node (ref "DCDC301") (pin "5") (pinfunction "SENSE_5") (pintype "input"))
      (node (ref "R306") (pin "1") (pinfunction "1_1") (pintype "passive"))
      (node (ref "SH301") (pin "2") (pinfunction "P$2_2") (pintype "bidirectional"))
    )
    (net (code "58") (name "SIMTRACE_LED_GREEN") (class "Default")
      (node (ref "LED201") (pin "K") (pinfunction "C_K") (pintype "passive"))
      (node (ref "U202") (pin "10") (pinfunction "A14/AD1/PCK2/RD/PA18_10") (pintype "bidirectional"))
    )
    (net (code "59") (name "SIMTRACE_LED_RED") (class "Default")
      (node (ref "LED202") (pin "C") (pinfunction "C_C") (pintype "passive"))
      (node (ref "U202") (pin "9") (pinfunction "PWMH3/AD0/PCK1/TD/PA17_9") (pintype "bidirectional"))
    )
    (net (code "60") (name "SLOT_CLK") (class "Default")
      (node (ref "C103") (pin "1") (pinfunction "1_1") (pintype "passive"))
      (node (ref "D101") (pin "5") (pinfunction "5_5") (pintype "passive"))
      (node (ref "IC201") (pin "4") (pinfunction "A_4") (pintype "bidirectional"))
      (node (ref "IC202") (pin "13") (pinfunction "A_13") (pintype "bidirectional"))
      (node (ref "SIM101") (pin "C3") (pinfunction "CLK_C3") (pintype "input"))
    )
    (net (code "61") (name "SLOT_DET") (class "Default")
      (node (ref "IC201") (pin "8") (pinfunction "A_8") (pintype "bidirectional"))
      (node (ref "R114") (pin "2") (pinfunction "2_2") (pintype "passive"))
      (node (ref "SIM101") (pin "CD1") (pinfunction "0_CD1") (pintype "passive"))
      (node (ref "U202") (pin "31") (pinfunction "PGMM0/XOUT32/CTS0/PA8_31") (pintype "bidirectional"))
    )
    (net (code "62") (name "SLOT_IO") (class "Default")
      (node (ref "C105") (pin "1") (pinfunction "1_1") (pintype "passive"))
      (node (ref "D101") (pin "4") (pinfunction "4_4") (pintype "passive"))
      (node (ref "IC201") (pin "2") (pinfunction "A_2") (pintype "bidirectional"))
      (node (ref "IC202") (pin "11") (pinfunction "A_11") (pintype "bidirectional"))
      (node (ref "R105") (pin "2") (pinfunction "2_2") (pintype "passive"))
      (node (ref "SIM101") (pin "C7") (pinfunction "I/O_C7") (pintype "bidirectional"))
    )
    (net (code "63") (name "SLOT_VDD") (class "Default")
      (node (ref "C106") (pin "1") (pinfunction "1_1") (pintype "passive"))
      (node (ref "D101") (pin "3") (pinfunction "3_3") (pintype "passive"))
      (node (ref "IC204") (pin "5") (pinfunction "OUT_5") (pintype "power_in"))
      (node (ref "IC205") (pin "5") (pinfunction "OUT_5") (pintype "power_in"))
      (node (ref "R105") (pin "1") (pinfunction "1_1") (pintype "passive"))
      (node (ref "SIM101") (pin "C1") (pinfunction "VCC_C1") (pintype "power_in"))
      (node (ref "TP2") (pin "TP") (pinfunction "TP_TP") (pintype "input"))
    )
    (net (code "64") (name "ST_DRXD") (class "Default")
      (node (ref "IC203") (pin "4") (pinfunction "2B_4") (pintype "passive"))
      (node (ref "R210") (pin "2") (pinfunction "2_2") (pintype "passive"))
      (node (ref "R214") (pin "1") (pinfunction "1_1") (pintype "passive"))
    )
    (net (code "65") (name "ST_DTXD") (class "Default")
      (node (ref "C219") (pin "1") (pinfunction "1_1") (pintype "passive"))
      (node (ref "IC203") (pin "3") (pinfunction "1B_3") (pintype "passive"))
      (node (ref "U202") (pin "29") (pinfunction "NPCS2/UTXD0/PA10_29") (pintype "bidirectional"))
    )
    (net (code "66") (name "ST_TCK") (class "Default")
      (node (ref "TC201") (pin "1") (pinfunction "1_1") (pintype "passive"))
      (node (ref "U202") (pin "53") (pinfunction "SWCLK/PB7/TCK_53") (pintype "bidirectional"))
    )
    (net (code "67") (name "ST_TDI") (class "Default")
      (node (ref "TC201") (pin "9") (pinfunction "9_9") (pintype "passive"))
      (node (ref "U202") (pin "33") (pinfunction "PB4/TDI_33") (pintype "bidirectional"))
    )
    (net (code "68") (name "ST_TDO") (class "Default")
      (node (ref "TC201") (pin "3") (pinfunction "3_3") (pintype "passive"))
      (node (ref "U202") (pin "49") (pinfunction "TRACESWO/PB5/TDO_49") (pintype "bidirectional"))
    )
    (net (code "69") (name "ST_TMS") (class "Default")
      (node (ref "TC201") (pin "5") (pinfunction "5_5") (pintype "passive"))
      (node (ref "U202") (pin "51") (pinfunction "SWDIO/PB6/TMS_51") (pintype "bidirectional"))
    )
    (net (code "70") (name "ST_UART1_CLK") (class "Default")
      (node (ref "IC202") (pin "7") (pinfunction "B_7") (pintype "bidirectional"))
      (node (ref "U202") (pin "15") (pinfunction "A19/PWMH0/SCK1/PA23_15") (pintype "bidirectional"))
      (node (ref "U202") (pin "41") (pinfunction "TCLK2/RI1/PA29_41") (pintype "bidirectional"))
    )
    (net (code "71") (name "ST_UART1_IO") (class "Default")
      (node (ref "IC202") (pin "9") (pinfunction "B_9") (pintype "bidirectional"))
      (node (ref "U202") (pin "11") (pinfunction "AD8/PCK1/RXD1/PA21_11") (pintype "bidirectional"))
      (node (ref "U202") (pin "14") (pinfunction "AD9/NPCS3/TXD1/PA22_14") (pintype "bidirectional"))
      (node (ref "U202") (pin "37") (pinfunction "TIOB2/DTR1/PA27_37") (pintype "bidirectional"))
    )
    (net (code "72") (name "ST_UART2_CLK") (class "Default")
      (node (ref "IC201") (pin "7") (pinfunction "B_7") (pintype "bidirectional"))
      (node (ref "U202") (pin "36") (pinfunction "PGMNCMD/PA4_36") (pintype "bidirectional"))
      (node (ref "U202") (pin "44") (pinfunction "PGMEN2/PA2_44") (pintype "bidirectional"))
    )
    (net (code "73") (name "ST_UART2_IO") (class "Default")
      (node (ref "IC201") (pin "9") (pinfunction "B_9") (pintype "bidirectional"))
      (node (ref "U202") (pin "34") (pinfunction "PGMNOE/TXD0/PA6_34") (pintype "bidirectional"))
      (node (ref "U202") (pin "35") (pinfunction "PGMRDY/RXD0/PA5_35") (pintype "bidirectional"))
      (node (ref "U202") (pin "47") (pinfunction "PGMEN1/PA1_47") (pintype "bidirectional"))
    )
    (net (code "74") (name "ST_USB_VBUS") (class "Default")
      (node (ref "U201") (pin "5") (pinfunction "VCC_5") (pintype "passive"))
      (node (ref "X201") (pin "1") (pinfunction "1_1") (pintype "input"))
    )
    (net (code "75") (name "TRIM") (class "Default")
      (node (ref "C312") (pin "1") (pinfunction "1_1") (pintype "passive"))
      (node (ref "DCDC301") (pin "6") (pinfunction "TRIM_6") (pintype "input"))
      (node (ref "R307") (pin "1") (pinfunction "1_1") (pintype "passive"))
    )
    (net (code "76") (name "USB3.0_RX_N") (class "Default")
      (node (ref "D102") (pin "9") (pinfunction "7_9") (pintype "passive"))
      (node (ref "NGFF101") (pin "35") (pinfunction "USB3.0_RX_N_35") (pintype "passive"))
      (node (ref "X102") (pin "9") (pinfunction "RX-_9") (pintype "passive"))
    )
    (net (code "77") (name "USB3.0_RX_P") (class "Default")
      (node (ref "D102") (pin "8") (pinfunction "6_8") (pintype "passive"))
      (node (ref "NGFF101") (pin "37") (pinfunction "USB3.0_RX_P_37") (pintype "passive"))
      (node (ref "X102") (pin "10") (pinfunction "RX+_10") (pintype "passive"))
    )
    (net (code "78") (name "USB3.0_TX_N") (class "Default")
      (node (ref "D102") (pin "12") (pinfunction "2_12") (pintype "passive"))
      (node (ref "NGFF101") (pin "29") (pinfunction "USB3.0_TX_N_29") (pintype "passive"))
      (node (ref "X102") (pin "6") (pinfunction "TX-_6") (pintype "passive"))
    )
    (net (code "79") (name "USB3.0_TX_P") (class "Default")
      (node (ref "D102") (pin "11") (pinfunction "1_11") (pintype "passive"))
      (node (ref "NGFF101") (pin "31") (pinfunction "USB3.0_TX_P_31") (pintype "passive"))
      (node (ref "X102") (pin "7") (pinfunction "TX+_7") (pintype "passive"))
    )
    (net (code "80") (name "VCC_1V8") (class "Default")
      (node (ref "C311") (pin "2") (pinfunction "2_2") (pintype "passive"))
      (node (ref "IC202") (pin "2") (pinfunction "A_2") (pintype "bidirectional"))
      (node (ref "R106") (pin "2") (pinfunction "2_2") (pintype "passive"))
      (node (ref "R108") (pin "2") (pinfunction "2_2") (pintype "passive"))
      (node (ref "R109") (pin "2") (pinfunction "2_2") (pintype "passive"))
      (node (ref "R110") (pin "2") (pinfunction "2_2") (pintype "passive"))
      (node (ref "R113") (pin "1") (pinfunction "1_1") (pintype "passive"))
      (node (ref "R115") (pin "2") (pinfunction "2_2") (pintype "passive"))
      (node (ref "U301") (pin "5") (pinfunction "OUT_5") (pintype "passive"))
      (node (ref "X101") (pin "5") (pinfunction "5_5") (pintype "passive"))
    )
    (net (code "81") (name "VCC_3V3") (class "Default")
      (node (ref "C203") (pin "2") (pinfunction "2_2") (pintype "passive"))
      (node (ref "C204") (pin "2") (pinfunction "2_2") (pintype "passive"))
      (node (ref "C206") (pin "2") (pinfunction "2_2") (pintype "passive"))
      (node (ref "C207") (pin "2") (pinfunction "2_2") (pintype "passive"))
      (node (ref "C213") (pin "2") (pinfunction "2_2") (pintype "passive"))
      (node (ref "C214") (pin "2") (pinfunction "2_2") (pintype "passive"))
      (node (ref "C215") (pin "2") (pinfunction "2_2") (pintype "passive"))
      (node (ref "C306") (pin "2") (pinfunction "2_2") (pintype "passive"))
      (node (ref "C307") (pin "1") (pinfunction "1_1") (pintype "passive"))
      (node (ref "C309") (pin "+") (pinfunction "+_+") (pintype "passive"))
      (node (ref "C310") (pin "1") (pinfunction "1_1") (pintype "bidirectional"))
      (node (ref "DCDC301") (pin "4") (pinfunction "VOUT_4") (pintype "passive"))
      (node (ref "IC201") (pin "20") (pinfunction "V+_20") (pintype "passive"))
      (node (ref "IC202") (pin "20") (pinfunction "V+_20") (pintype "passive"))
      (node (ref "IC203") (pin "5") (pinfunction "VCC_5") (pintype "passive"))
      (node (ref "IC204") (pin "1") (pinfunction "IN_1") (pintype "passive"))
      (node (ref "IC301") (pin "1") (pinfunction "VIN_1") (pintype "power_in"))
      (node (ref "IC301") (pin "3") (pinfunction "VBIAS_3") (pintype "power_in"))
      (node (ref "IC301") (pin "4") (pinfunction "VIN_4") (pintype "power_in"))
      (node (ref "IC302") (pin "1") (pinfunction "VIN_1") (pintype "power_in"))
      (node (ref "IC302") (pin "3") (pinfunction "VBIAS_3") (pintype "power_in"))
      (node (ref "IC302") (pin "4") (pinfunction "VIN_4") (pintype "power_in"))
      (node (ref "L202") (pin "1") (pinfunction "1_1") (pintype "passive"))
      (node (ref "LED301") (pin "A") (pinfunction "A_A") (pintype "passive"))
      (node (ref "R201") (pin "2") (pinfunction "2_2") (pintype "passive"))
      (node (ref "R203") (pin "1") (pinfunction "1_1") (pintype "passive"))
      (node (ref "R204") (pin "1") (pinfunction "1_1") (pintype "passive"))
      (node (ref "R209") (pin "2") (pinfunction "2_2") (pintype "passive"))
      (node (ref "R214") (pin "2") (pinfunction "2_2") (pintype "passive"))
      (node (ref "R215") (pin "1") (pinfunction "1_1") (pintype "passive"))
      (node (ref "R217") (pin "2") (pinfunction "2_2") (pintype "passive"))
      (node (ref "R218") (pin "1") (pinfunction "1_1") (pintype "passive"))
      (node (ref "R220") (pin "1") (pinfunction "1_1") (pintype "passive"))
      (node (ref "R221") (pin "1") (pinfunction "1_1") (pintype "passive"))
      (node (ref "R304") (pin "1") (pinfunction "1_1") (pintype "passive"))
      (node (ref "R311") (pin "2") (pinfunction "2_2") (pintype "passive"))
      (node (ref "SH301") (pin "1") (pinfunction "P$1_1") (pintype "bidirectional"))
      (node (ref "TC201") (pin "4") (pinfunction "4_4") (pintype "passive"))
      (node (ref "U202") (pin "18") (pinfunction "VDDIO_18") (pintype "power_in"))
      (node (ref "U202") (pin "45") (pinfunction "VDDIO_45") (pintype "power_in"))
      (node (ref "U202") (pin "58") (pinfunction "VDDIO_58") (pintype "power_in"))
      (node (ref "U202") (pin "7") (pinfunction "VDDIN_7") (pintype "power_in"))
    )
    (net (code "82") (name "VDD_1V8_SIMTRACE12") (class "Default")
      (node (ref "C205") (pin "2") (pinfunction "2_2") (pintype "passive"))
      (node (ref "C208") (pin "2") (pinfunction "2_2") (pintype "passive"))
      (node (ref "C209") (pin "2") (pinfunction "2_2") (pintype "passive"))
      (node (ref "C210") (pin "2") (pinfunction "2_2") (pintype "passive"))
      (node (ref "C211") (pin "2") (pinfunction "2_2") (pintype "passive"))
      (node (ref "U202") (pin "12") (pinfunction "VDDCORE_12") (pintype "bidirectional"))
      (node (ref "U202") (pin "24") (pinfunction "VDDCORE_24") (pintype "bidirectional"))
      (node (ref "U202") (pin "54") (pinfunction "VDDCORE_54") (pintype "bidirectional"))
      (node (ref "U202") (pin "64") (pinfunction "VDDPLL_64") (pintype "bidirectional"))
      (node (ref "U202") (pin "8") (pinfunction "VDDOUT_8") (pintype "bidirectional"))
    )
    (net (code "83") (name "VERSION_DETECT") (class "Default")
      (node (ref "R218") (pin "2") (pinfunction "2_2") (pintype "passive"))
      (node (ref "R219") (pin "2") (pinfunction "2_2") (pintype "passive"))
      (node (ref "U202") (pin "13") (pinfunction "A15/AD2/PWML0/RK/PA19_13") (pintype "bidirectional"))
    )
    (net (code "84") (name "V_MODEM") (class "Default")
      (node (ref "C107") (pin "2") (pinfunction "2_2") (pintype "passive"))
      (node (ref "C108") (pin "2") (pinfunction "2_2") (pintype "passive"))
      (node (ref "C109") (pin "2") (pinfunction "2_2") (pintype "passive"))
      (node (ref "C110") (pin "1") (pinfunction "1_1") (pintype "passive"))
      (node (ref "C111") (pin "1") (pinfunction "1_1") (pintype "passive"))
      (node (ref "C112") (pin "2") (pinfunction "2_2") (pintype "passive"))
      (node (ref "C113") (pin "2") (pinfunction "2_2") (pintype "passive"))
      (node (ref "C114") (pin "2") (pinfunction "2_2") (pintype "passive"))
      (node (ref "C115") (pin "1") (pinfunction "1_1") (pintype "passive"))
      (node (ref "C116") (pin "1") (pinfunction "1_1") (pintype "passive"))
      (node (ref "C308") (pin "2") (pinfunction "2_2") (pintype "passive"))
      (node (ref "IC301") (pin "5") (pinfunction "VOUT_5") (pintype "power_in"))
      (node (ref "IC301") (pin "8") (pinfunction "VOUT_8") (pintype "power_in"))
      (node (ref "IC302") (pin "5") (pinfunction "VOUT_5") (pintype "power_in"))
      (node (ref "IC302") (pin "8") (pinfunction "VOUT_8") (pintype "power_in"))
      (node (ref "LED101") (pin "A") (pinfunction "A_A") (pintype "passive"))
      (node (ref "NGFF101") (pin "2") (pinfunction "3.3V_2") (pintype "power_in"))
      (node (ref "NGFF101") (pin "4") (pinfunction "3.3V_4") (pintype "power_in"))
      (node (ref "NGFF101") (pin "70") (pinfunction "3.3V_70") (pintype "power_in"))
      (node (ref "NGFF101") (pin "72") (pinfunction "3.3V_72") (pintype "power_in"))
      (node (ref "NGFF101") (pin "74") (pinfunction "3.3V_74") (pintype "power_in"))
      (node (ref "R111") (pin "1") (pinfunction "1_1") (pintype "passive"))
      (node (ref "U301") (pin "1") (pinfunction "IN_1") (pintype "input"))
      (node (ref "U301") (pin "3") (pinfunction "EN_3") (pintype "input"))
    )
    (net (code "85") (name "WWAN") (class "Default")
      (node (ref "NGFF101") (pin "10") (pinfunction "~{LED}_10") (pintype "output"))
      (node (ref "R107") (pin "2") (pinfunction "2_2") (pintype "passive"))
      (node (ref "R211") (pin "1") (pinfunction "1_1") (pintype "passive"))
    )
    (net (code "86") (name "_NGFF_USB_D_N") (class "Default")
      (node (ref "D102") (pin "14") (pinfunction "5_14") (pintype "passive"))
      (node (ref "NGFF101") (pin "9") (pinfunction "USB_D_N_9") (pintype "passive"))
      (node (ref "X102") (pin "2") (pinfunction "D-_2") (pintype "passive"))
    )
    (net (code "87") (name "_NGFF_USB_D_P") (class "Default")
      (node (ref "D102") (pin "13") (pinfunction "4_13") (pintype "passive"))
      (node (ref "NGFF101") (pin "7") (pinfunction "USB_D_P_7") (pintype "passive"))
      (node (ref "X102") (pin "3") (pinfunction "D+_3") (pintype "passive"))
    )
    (net (code "88") (name "_USIM1_CLK") (class "Default")
      (node (ref "NGFF101") (pin "32") (pinfunction "UIM_CLK_32") (pintype "output"))
      (node (ref "R117") (pin "1") (pinfunction "1_1") (pintype "passive"))
    )
    (net (code "89") (name "_USIM1_DATA") (class "Default")
      (node (ref "NGFF101") (pin "34") (pinfunction "UIM_DATA_34") (pintype "bidirectional"))
      (node (ref "R119") (pin "1") (pinfunction "1_1") (pintype "passive"))
    )
    (net (code "90") (name "_~{USIM1_RESET}") (class "Default")
      (node (ref "NGFF101") (pin "30") (pinfunction "~{UIM_RESET}_30") (pintype "output"))
      (node (ref "R118") (pin "1") (pinfunction "1_1") (pintype "passive"))
    )
    (net (code "91") (name "unconnected-(D101-Pad1)") (class "Default")
      (node (ref "D101") (pin "1") (pinfunction "1_1") (pintype "passive"))
    )
    (net (code "92") (name "unconnected-(IC202B-A-Pad4)") (class "Default")
      (node (ref "IC202") (pin "4") (pinfunction "A_4") (pintype "bidirectional"))
    )
    (net (code "93") (name "unconnected-(IC202B-B-Pad16)") (class "Default")
      (node (ref "IC202") (pin "16") (pinfunction "B_16") (pintype "bidirectional"))
    )
    (net (code "94") (name "unconnected-(IC202C-A-Pad6)") (class "Default")
      (node (ref "IC202") (pin "6") (pinfunction "A_6") (pintype "bidirectional"))
    )
    (net (code "95") (name "unconnected-(IC202C-B-Pad14)") (class "Default")
      (node (ref "IC202") (pin "14") (pinfunction "B_14") (pintype "bidirectional"))
    )
    (net (code "96") (name "unconnected-(IC202D-A-Pad8)") (class "Default")
      (node (ref "IC202") (pin "8") (pinfunction "A_8") (pintype "bidirectional"))
    )
    (net (code "97") (name "unconnected-(IC202D-B-Pad12)") (class "Default")
      (node (ref "IC202") (pin "12") (pinfunction "B_12") (pintype "bidirectional"))
    )
    (net (code "98") (name "unconnected-(IC202H-A-Pad17)") (class "Default")
      (node (ref "IC202") (pin "17") (pinfunction "A_17") (pintype "bidirectional"))
    )
    (net (code "99") (name "unconnected-(IC202H-B-Pad3)") (class "Default")
      (node (ref "IC202") (pin "3") (pinfunction "B_3") (pintype "bidirectional"))
    )
    (net (code "100") (name "unconnected-(IC205-~{FLAG}-Pad4)") (class "Default")
      (node (ref "IC205") (pin "4") (pinfunction "~{FLAG}_4") (pintype "input"))
    )
    (net (code "101") (name "unconnected-(NGFF101A-ANTCTL0-Pad59)") (class "Default")
      (node (ref "NGFF101") (pin "59") (pinfunction "ANTCTL0_59") (pintype "output"))
    )
    (net (code "102") (name "unconnected-(NGFF101A-ANTCTL1-Pad61)") (class "Default")
      (node (ref "NGFF101") (pin "61") (pinfunction "ANTCTL1_61") (pintype "output"))
    )
    (net (code "103") (name "unconnected-(NGFF101A-ANTCTL2-Pad63)") (class "Default")
      (node (ref "NGFF101") (pin "63") (pinfunction "ANTCTL2_63") (pintype "output"))
    )
    (net (code "104") (name "unconnected-(NGFF101A-ANTCTL3-Pad65)") (class "Default")
      (node (ref "NGFF101") (pin "65") (pinfunction "ANTCTL3_65") (pintype "output"))
    )
    (net (code "105") (name "unconnected-(NGFF101A-COEX1-Pad64)") (class "Default")
      (node (ref "NGFF101") (pin "64") (pinfunction "COEX1_64") (pintype "bidirectional"))
    )
    (net (code "106") (name "unconnected-(NGFF101A-COEX2-Pad62)") (class "Default")
      (node (ref "NGFF101") (pin "62") (pinfunction "COEX2_62") (pintype "bidirectional"))
    )
    (net (code "107") (name "unconnected-(NGFF101A-COEX3-Pad60)") (class "Default")
      (node (ref "NGFF101") (pin "60") (pinfunction "COEX3_60") (pintype "bidirectional"))
    )
    (net (code "108") (name "unconnected-(NGFF101A-CONFIG_0-Pad21)") (class "Default")
      (node (ref "NGFF101") (pin "21") (pinfunction "CONFIG_0_21") (pintype "bidirectional"))
    )
    (net (code "109") (name "unconnected-(NGFF101A-CONFIG_1-Pad69)") (class "Default")
      (node (ref "NGFF101") (pin "69") (pinfunction "CONFIG_1_69") (pintype "output"))
    )
    (net (code "110") (name "unconnected-(NGFF101A-CONFIG_2-Pad75)") (class "Default")
      (node (ref "NGFF101") (pin "75") (pinfunction "CONFIG_2_75") (pintype "output"))
    )
    (net (code "111") (name "unconnected-(NGFF101A-CONFIG_3-Pad1)") (class "Default")
      (node (ref "NGFF101") (pin "1") (pinfunction "CONFIG_3_1") (pintype "bidirectional"))
    )
    (net (code "112") (name "unconnected-(NGFF101A-I2C_IRQ_HW{slash}UIM2_CLK_SIWI-Pad44)") (class "Default")
      (node (ref "NGFF101") (pin "44") (pinfunction "I2C_IRQ_HW/UIM2_CLK_SIWI_44") (pintype "input"))
    )
    (net (code "113") (name "unconnected-(NGFF101A-I2C_SCL_HW{slash}SIM_DET2_SIWI-Pad40)") (class "Default")
      (node (ref "NGFF101") (pin "40") (pinfunction "I2C_SCL_HW/SIM_DET2_SIWI_40") (pintype "output"))
    )
    (net (code "114") (name "unconnected-(NGFF101A-I2C_SCL_SIWI-Pad58)") (class "Default")
      (node (ref "NGFF101") (pin "58") (pinfunction "I2C_SCL_SIWI_58") (pintype "output"))
    )
    (net (code "115") (name "unconnected-(NGFF101A-I2C_SDA_HW{slash}UIM2_DATA_SIWI-Pad42)") (class "Default")
      (node (ref "NGFF101") (pin "42") (pinfunction "I2C_SDA_HW/UIM2_DATA_SIWI_42") (pintype "bidirectional"))
    )
    (net (code "116") (name "unconnected-(NGFF101A-I2C_SDA_SIWI-Pad56)") (class "Default")
      (node (ref "NGFF101") (pin "56") (pinfunction "I2C_SDA_SIWI_56") (pintype "bidirectional"))
    )
    (net (code "117") (name "unconnected-(NGFF101A-SYSCLK_HW{slash}UIM2_RESET_SIWI-Pad46)") (class "Default")
      (node (ref "NGFF101") (pin "46") (pinfunction "SYSCLK_HW/UIM2_RESET_SIWI_46") (pintype "output"))
    )
    (net (code "118") (name "unconnected-(NGFF101A-TX_BLANKING_HW{slash}UIM2_PWR_SIWI-Pad48)") (class "Default")
      (node (ref "NGFF101") (pin "48") (pinfunction "TX_BLANKING_HW/UIM2_PWR_SIWI_48") (pintype "output"))
    )
    (net (code "119") (name "unconnected-(SIM101B-VPP-PadC6)") (class "Default")
      (node (ref "SIM101") (pin "C6") (pinfunction "VPP_C6") (pintype "power_in"))
    )
    (net (code "120") (name "unconnected-(TC201-Pad7)") (class "Default")
      (node (ref "TC201") (pin "7") (pinfunction "7_7") (pintype "passive"))
    )
    (net (code "121") (name "unconnected-(TC201-Pad8)") (class "Default")
      (node (ref "TC201") (pin "8") (pinfunction "8_8") (pintype "passive"))
    )
    (net (code "122") (name "unconnected-(U202-PA3-Pad43)") (class "Default")
      (node (ref "U202") (pin "43") (pinfunction "PA3_43") (pintype "bidirectional"))
    )
    (net (code "123") (name "unconnected-(U202-PB13{slash}DAC0-Pad59)") (class "Default")
      (node (ref "U202") (pin "59") (pinfunction "PB13/DAC0_59") (pintype "bidirectional"))
    )
    (net (code "124") (name "unconnected-(U202-PB14{slash}DAC1-Pad63)") (class "Default")
      (node (ref "U202") (pin "63") (pinfunction "PB14/DAC1_63") (pintype "bidirectional"))
    )
    (net (code "125") (name "unconnected-(U202-PWMH1{slash}MISO{slash}PA12-Pad27)") (class "Default")
      (node (ref "U202") (pin "27") (pinfunction "PWMH1/MISO/PA12_27") (pintype "bidirectional"))
    )
    (net (code "126") (name "unconnected-(U202-TST-Pad40)") (class "Default")
      (node (ref "U202") (pin "40") (pinfunction "TST_40") (pintype "bidirectional"))
    )
    (net (code "127") (name "unconnected-(X102-ID-Pad4)") (class "Default")
      (node (ref "X102") (pin "4") (pinfunction "ID_4") (pintype "passive"))
    )
    (net (code "128") (name "unconnected-(X201-Pad4)") (class "Default")
      (node (ref "X201") (pin "4") (pinfunction "4_4") (pintype "input"))
    )
    (net (code "129") (name "unconnected-(X201B-S2-PadM2)") (class "Default")
      (node (ref "X201") (pin "M2") (pinfunction "S2_M2") (pintype "passive"))
    )
    (net (code "130") (name "unconnected-(X201B-S3-PadM3)") (class "Default")
      (node (ref "X201") (pin "M3") (pinfunction "S3_M3") (pintype "passive"))
    )
    (net (code "131") (name "~{ALARM_ST_SIM_VDD}") (class "Default")
      (node (ref "IC204") (pin "4") (pinfunction "~{FLAG}_4") (pintype "input"))
      (node (ref "R215") (pin "2") (pinfunction "2_2") (pintype "passive"))
      (node (ref "U202") (pin "21") (pinfunction "PWMH3/SPCK/PA14_21") (pintype "bidirectional"))
    )
    (net (code "132") (name "~{CONNECT_MDM_SIM}") (class "Default")
      (node (ref "IC201") (pin "1") (pinfunction "~{1OE}_1") (pintype "input"))
      (node (ref "R205") (pin "1") (pinfunction "1_1") (pintype "passive"))
      (node (ref "U202") (pin "48") (pinfunction "PGMEN0/PA0_48") (pintype "bidirectional"))
    )
    (net (code "133") (name "~{CONNECT_UART1}") (class "Default")
      (node (ref "IC202") (pin "19") (pinfunction "~{2OE}_19") (pintype "input"))
      (node (ref "R220") (pin "2") (pinfunction "2_2") (pintype "passive"))
      (node (ref "U202") (pin "16") (pinfunction "A16/AD3/PWML1/RF/PA20_16") (pintype "bidirectional"))
    )
    (net (code "134") (name "~{CONNECT_UART2}") (class "Default")
      (node (ref "IC201") (pin "19") (pinfunction "~{2OE}_19") (pintype "input"))
      (node (ref "R221") (pin "2") (pinfunction "2_2") (pintype "passive"))
      (node (ref "U202") (pin "38") (pinfunction "TCLK1/DSR1/PA28_38") (pintype "bidirectional"))
    )
    (net (code "135") (name "~{GPS_DISABLE}") (class "Default")
      (node (ref "NGFF101") (pin "26") (pinfunction "~{GPS_DISABLE}_26") (pintype "input"))
      (node (ref "R110") (pin "1") (pinfunction "1_1") (pintype "passive"))
      (node (ref "X103") (pin "4") (pinfunction "4_4") (pintype "passive"))
    )
    (net (code "136") (name "~{MDM_UIM_RST}") (class "Default")
      (node (ref "IC201") (pin "14") (pinfunction "B_14") (pintype "bidirectional"))
      (node (ref "IC201") (pin "15") (pinfunction "A_15") (pintype "bidirectional"))
      (node (ref "R118") (pin "2") (pinfunction "2_2") (pintype "passive"))
    )
    (net (code "137") (name "~{NGFF_RESET}") (class "Default")
      (node (ref "C102") (pin "1") (pinfunction "1_1") (pintype "passive"))
      (node (ref "NGFF101") (pin "67") (pinfunction "~{RESET}_67") (pintype "input"))
      (node (ref "R106") (pin "1") (pinfunction "1_1") (pintype "passive"))
      (node (ref "T102") (pin "C") (pinfunction "C_C") (pintype "passive"))
      (node (ref "X103") (pin "2") (pinfunction "2_2") (pintype "passive"))
    )
    (net (code "138") (name "~{PWR_ON}") (class "Default")
      (node (ref "R101") (pin "1") (pinfunction "1_1") (pintype "passive"))
      (node (ref "R103") (pin "2") (pinfunction "2_2") (pintype "passive"))
      (node (ref "U202") (pin "26") (pinfunction "TIOA2/DCD1/PA26_26") (pintype "bidirectional"))
    )
    (net (code "139") (name "~{SET_SIM_DET}") (class "Default")
      (node (ref "IC202") (pin "1") (pinfunction "~{1OE}_1") (pintype "input"))
      (node (ref "R204") (pin "2") (pinfunction "2_2") (pintype "passive"))
      (node (ref "U202") (pin "22") (pinfunction "PWMH2/MOSI/PA13_22") (pintype "bidirectional"))
    )
    (net (code "140") (name "~{SIMTRACE_RESET}") (class "Default")
      (node (ref "R209") (pin "1") (pinfunction "1_1") (pintype "passive"))
      (node (ref "TC201") (pin "6") (pinfunction "6_6") (pintype "passive"))
      (node (ref "U202") (pin "39") (pinfunction "NRST_39") (pintype "bidirectional"))
    )
    (net (code "141") (name "~{SLOT_RST}") (class "Default")
      (node (ref "C104") (pin "1") (pinfunction "1_1") (pintype "passive"))
      (node (ref "D101") (pin "6") (pinfunction "6_6") (pintype "passive"))
      (node (ref "IC201") (pin "6") (pinfunction "A_6") (pintype "bidirectional"))
      (node (ref "IC202") (pin "15") (pinfunction "A_15") (pintype "bidirectional"))
      (node (ref "SIM101") (pin "C2") (pinfunction "RST_C2") (pintype "input"))
    )
    (net (code "142") (name "~{ST_UART1_RST}") (class "Default")
      (node (ref "IC202") (pin "5") (pinfunction "B_5") (pintype "bidirectional"))
      (node (ref "U202") (pin "23") (pinfunction "A20/PWMH1/RTS1/PA24_23") (pintype "bidirectional"))
    )
    (net (code "143") (name "~{ST_UART2_RST}") (class "Default")
      (node (ref "IC201") (pin "5") (pinfunction "B_5") (pintype "bidirectional"))
      (node (ref "U202") (pin "32") (pinfunction "PGMNVALID/XIN32/RTS0/PA7_32") (pintype "bidirectional"))
    )
    (net (code "144") (name "~{WAKE_ON_WWAN}") (class "Default")
      (node (ref "NGFF101") (pin "23") (pinfunction "~{WAKE_ON_WWAN}_23") (pintype "output"))
      (node (ref "R108") (pin "1") (pinfunction "1_1") (pintype "passive"))
    )
    (net (code "145") (name "~{W_DISABLE}") (class "Default")
      (node (ref "NGFF101") (pin "8") (pinfunction "~{W_DISABLE}_8") (pintype "input"))
      (node (ref "R115") (pin "1") (pinfunction "1_1") (pintype "passive"))
      (node (ref "X103") (pin "6") (pinfunction "6_6") (pintype "passive"))
    )
  )
)
